# main.net
KiCad netlist of a schematic drawn in Altium Designer
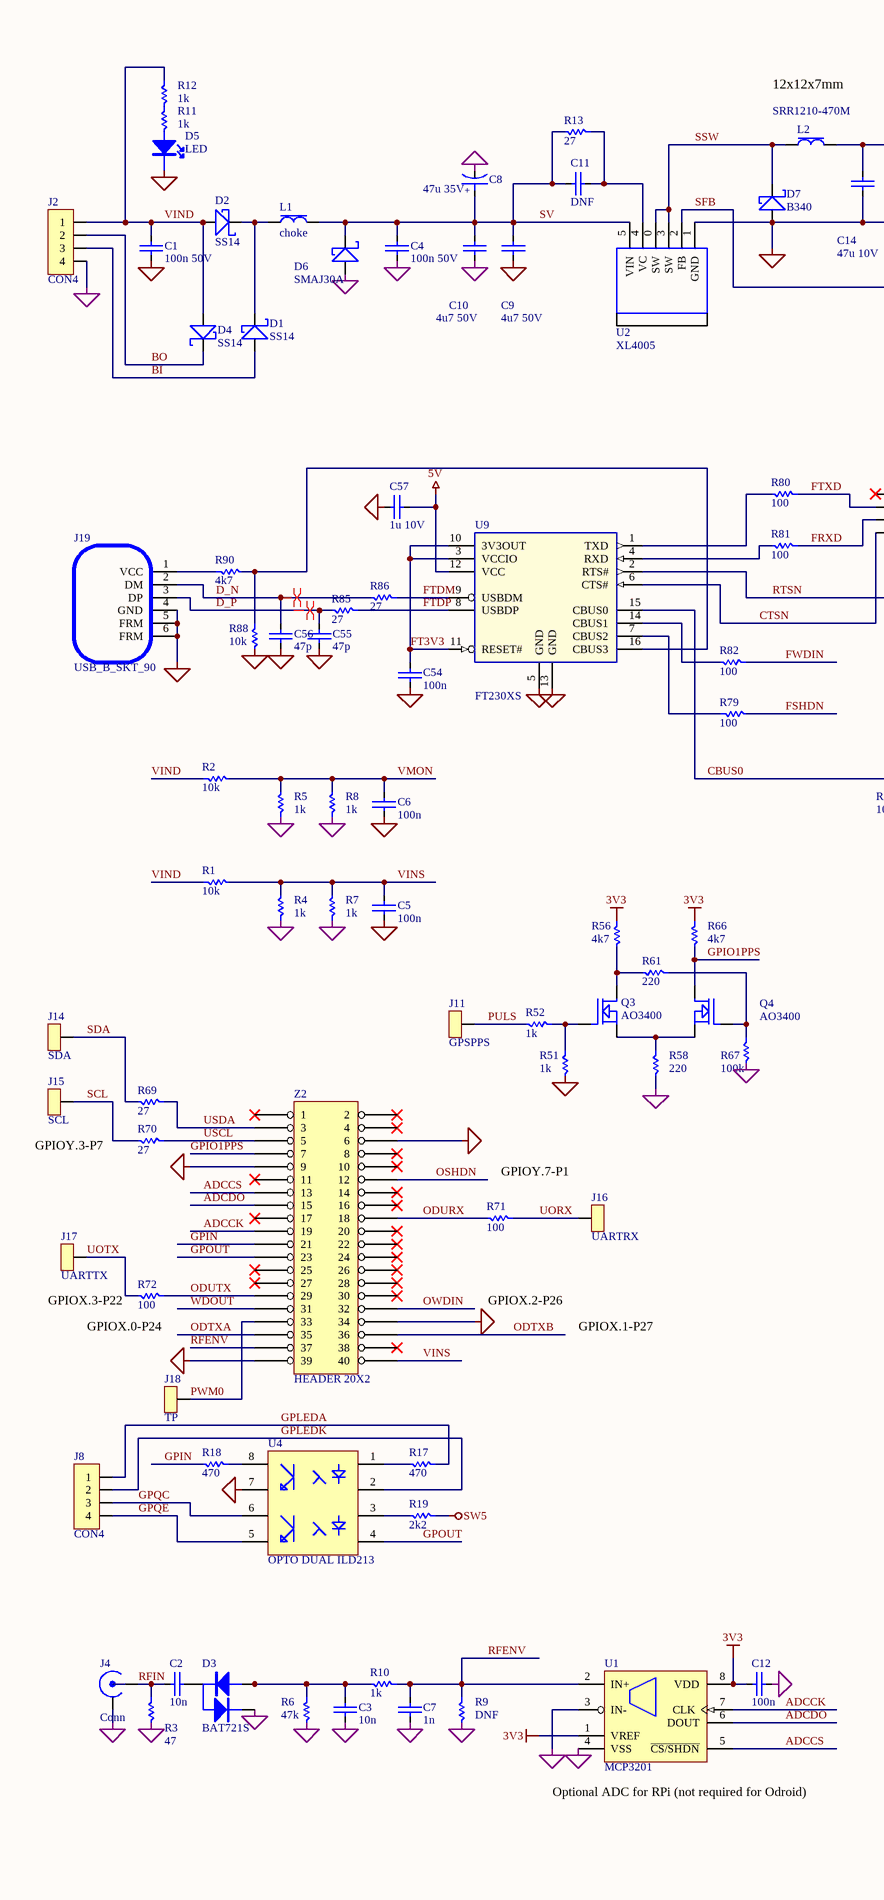
[diagram p0: main.SchDoc, left]
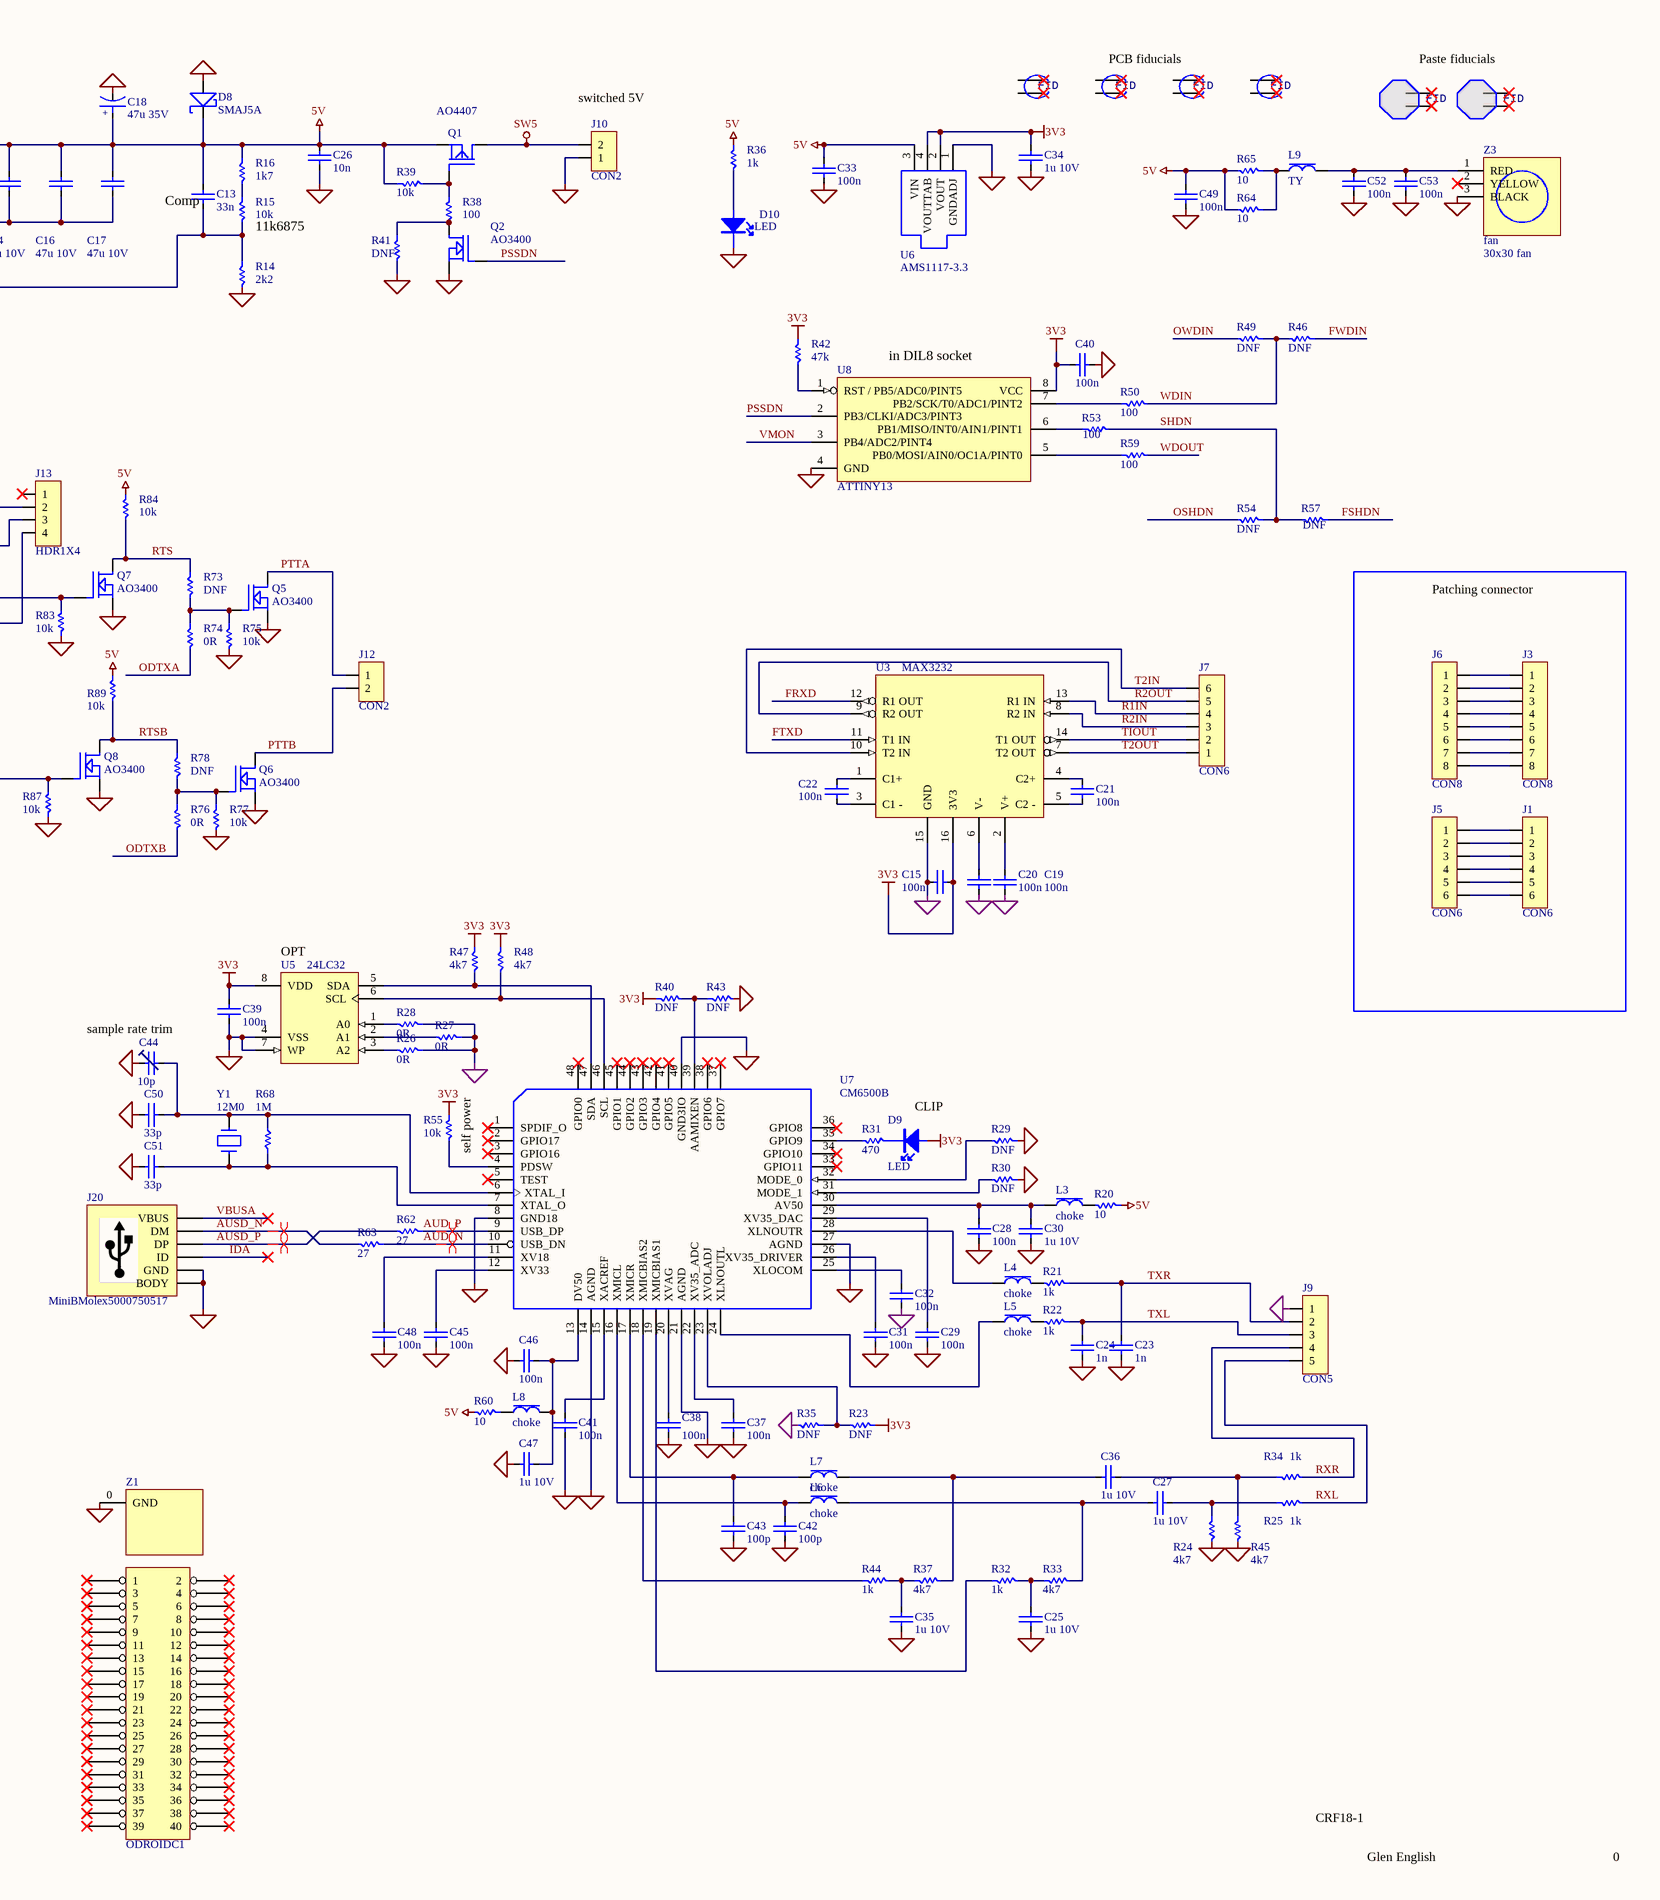
[diagram p1: main.SchDoc, right]

(export (version "E")
  (design (tool "Eeschema 10.0.6"))
  (components
    (comp (ref "C1")
      (value "100n 50V")
      (footprint "glensPCB:0603C")
      (libsource (lib "glen_sch") (part "CAPS"))
    )
    (comp (ref "C2") (value "10n") (footprint "glensPCB:0603C") (libsource (lib "glen_sch") (part "CAPS")))
    (comp (ref "C3") (value "10n") (footprint "glensPCB:0603C") (libsource (lib "glen_sch") (part "CAPS")))
    (comp (ref "C4")
      (value "100n 50V")
      (footprint "glensPCB:0603C")
      (libsource (lib "glen_sch") (part "CAPS"))
    )
    (comp (ref "C5") (value "100n") (footprint "glensPCB:0603C") (libsource (lib "glen_sch") (part "CAPS")))
    (comp (ref "C6") (value "100n") (footprint "glensPCB:0603C") (libsource (lib "glen_sch") (part "CAPS")))
    (comp (ref "C7") (value "1n") (footprint "glensPCB:0603C") (libsource (lib "glen_sch") (part "CAPS")))
    (comp (ref "C8")
      (value "47u 35V")
      (footprint "D_CASE_ELECTRO")
      (description "capacitor polarized")
      (libsource (lib "glen_sch") (part "CAP-POLS"))
    )
    (comp (ref "C9")
      (value "4u7 50V")
      (footprint "glensPCB:1206C")
      (libsource (lib "glen_sch") (part "CAPS"))
    )
    (comp (ref "C10")
      (value "4u7 50V")
      (footprint "glensPCB:1206C")
      (libsource (lib "glen_sch") (part "CAPS"))
    )
    (comp (ref "C11") (value "DNF") (footprint "glensPCB:0603C") (libsource (lib "glen_sch") (part "CAPS")))
    (comp (ref "C12") (value "100n") (footprint "glensPCB:0603C") (libsource (lib "glen_sch") (part "CAPS")))
    (comp (ref "C13") (value "33n") (footprint "glensPCB:0603C") (libsource (lib "glen_sch") (part "CAPS")))
    (comp (ref "C14")
      (value "47u 10V")
      (footprint "glensPCB:1206C")
      (libsource (lib "glen_sch") (part "CAPS"))
    )
    (comp (ref "C15") (value "100n") (footprint "glensPCB:0603C") (libsource (lib "glen_sch") (part "CAPS")))
    (comp (ref "C16")
      (value "47u 10V")
      (footprint "glensPCB:1206C")
      (libsource (lib "glen_sch") (part "CAPS"))
    )
    (comp (ref "C17")
      (value "47u 10V")
      (footprint "glensPCB:1206C")
      (libsource (lib "glen_sch") (part "CAPS"))
    )
    (comp (ref "C18")
      (value "47u 35V")
      (footprint "D_CASE_ELECTRO")
      (description "capacitor polarized")
      (libsource (lib "glen_sch") (part "CAP-POLS"))
    )
    (comp (ref "C19") (value "100n") (footprint "glensPCB:0603C") (libsource (lib "glen_sch") (part "CAPS")))
    (comp (ref "C20") (value "100n") (footprint "glensPCB:0603C") (libsource (lib "glen_sch") (part "CAPS")))
    (comp (ref "C21") (value "100n") (footprint "glensPCB:0603C") (libsource (lib "glen_sch") (part "CAPS")))
    (comp (ref "C22") (value "100n") (footprint "glensPCB:0603C") (libsource (lib "glen_sch") (part "CAPS")))
    (comp (ref "C23") (value "1n") (footprint "glensPCB:0603C") (libsource (lib "glen_sch") (part "CAPS")))
    (comp (ref "C24") (value "1n") (footprint "glensPCB:0603C") (libsource (lib "glen_sch") (part "CAPS")))
    (comp (ref "C25")
      (value "1u 10V")
      (footprint "glensPCB:0603C")
      (libsource (lib "glen_sch") (part "CAPS"))
    )
    (comp (ref "C26") (value "10n") (footprint "glensPCB:0603C") (libsource (lib "glen_sch") (part "CAPS")))
    (comp (ref "C27")
      (value "1u 10V")
      (footprint "glensPCB:0603C")
      (libsource (lib "glen_sch") (part "CAPS"))
    )
    (comp (ref "C28") (value "100n") (footprint "glensPCB:0603C") (libsource (lib "glen_sch") (part "CAPS")))
    (comp (ref "C29") (value "100n") (footprint "glensPCB:0603C") (libsource (lib "glen_sch") (part "CAPS")))
    (comp (ref "C30")
      (value "1u 10V")
      (footprint "glensPCB:0603C")
      (libsource (lib "glen_sch") (part "CAPS"))
    )
    (comp (ref "C31") (value "100n") (footprint "glensPCB:0603C") (libsource (lib "glen_sch") (part "CAPS")))
    (comp (ref "C32") (value "100n") (footprint "glensPCB:0603C") (libsource (lib "glen_sch") (part "CAPS")))
    (comp (ref "C33") (value "100n") (footprint "glensPCB:0603C") (libsource (lib "glen_sch") (part "CAPS")))
    (comp (ref "C34")
      (value "1u 10V")
      (footprint "glensPCB:0603C")
      (libsource (lib "glen_sch") (part "CAPS"))
    )
    (comp (ref "C35")
      (value "1u 10V")
      (footprint "glensPCB:0603C")
      (libsource (lib "glen_sch") (part "CAPS"))
    )
    (comp (ref "C36")
      (value "1u 10V")
      (footprint "glensPCB:0603C")
      (libsource (lib "glen_sch") (part "CAPS"))
    )
    (comp (ref "C37") (value "100n") (footprint "glensPCB:0603C") (libsource (lib "glen_sch") (part "CAPS")))
    (comp (ref "C38") (value "100n") (footprint "glensPCB:0603C") (libsource (lib "glen_sch") (part "CAPS")))
    (comp (ref "C39") (value "100n") (footprint "glensPCB:0603C") (libsource (lib "glen_sch") (part "CAPS")))
    (comp (ref "C40") (value "100n") (footprint "glensPCB:0603C") (libsource (lib "glen_sch") (part "CAPS")))
    (comp (ref "C41") (value "100n") (footprint "glensPCB:0603C") (libsource (lib "glen_sch") (part "CAPS")))
    (comp (ref "C42") (value "100p") (footprint "glensPCB:0603C") (libsource (lib "glen_sch") (part "CAPS")))
    (comp (ref "C43") (value "100p") (footprint "glensPCB:0603C") (libsource (lib "glen_sch") (part "CAPS")))
    (comp (ref "C44")
      (value "10p")
      (footprint "glensPCB:CAP0.1")
      (description "trimmer cap")
      (libsource (lib "glen_sch") (part "CAPTRIM"))
    )
    (comp (ref "C45") (value "100n") (footprint "glensPCB:0603C") (libsource (lib "glen_sch") (part "CAPS")))
    (comp (ref "C46") (value "100n") (footprint "glensPCB:0603C") (libsource (lib "glen_sch") (part "CAPS")))
    (comp (ref "C47")
      (value "1u 10V")
      (footprint "glensPCB:0603C")
      (libsource (lib "glen_sch") (part "CAPS"))
    )
    (comp (ref "C48") (value "100n") (footprint "glensPCB:0603C") (libsource (lib "glen_sch") (part "CAPS")))
    (comp (ref "C49") (value "100n") (footprint "glensPCB:0603C") (libsource (lib "glen_sch") (part "CAPS")))
    (comp (ref "C50") (value "33p") (footprint "glensPCB:0603C") (libsource (lib "glen_sch") (part "CAPS")))
    (comp (ref "C51") (value "33p") (footprint "glensPCB:0603C") (libsource (lib "glen_sch") (part "CAPS")))
    (comp (ref "C52") (value "100n") (footprint "glensPCB:0603C") (libsource (lib "glen_sch") (part "CAPS")))
    (comp (ref "C53") (value "100n") (footprint "glensPCB:0603C") (libsource (lib "glen_sch") (part "CAPS")))
    (comp (ref "C54") (value "100n") (footprint "glensPCB:0603C") (libsource (lib "glen_sch") (part "CAPS")))
    (comp (ref "C55") (value "47p") (footprint "glensPCB:0603C") (libsource (lib "glen_sch") (part "CAPS")))
    (comp (ref "C56") (value "47p") (footprint "glensPCB:0603C") (libsource (lib "glen_sch") (part "CAPS")))
    (comp (ref "C57")
      (value "1u 10V")
      (footprint "glensPCB:0603C")
      (libsource (lib "glen_sch") (part "CAPS"))
    )
    (comp (ref "D1")
      (value "SS14")
      (footprint "SMA_DIODE")
      (description "schottky")
      (libsource (lib "glen_sch") (part "DIODE_SHOTT_AK_SMALL"))
    )
    (comp (ref "D2")
      (value "SS14")
      (footprint "SMA_DIODE")
      (description "schottky")
      (libsource (lib "glen_sch") (part "DIODE_SHOTT_AK_SMALL"))
    )
    (comp (ref "D3")
      (value "BAT721S")
      (footprint "SOT23")
      (description "dual diode series")
      (libsource (lib "glen_sch") (part "BAT721A-DUALDIODE_COM_ANODE_1"))
    )
    (comp (ref "D4")
      (value "SS14")
      (footprint "SMA_DIODE")
      (description "schottky")
      (libsource (lib "glen_sch") (part "DIODE_SHOTT_AK_SMALL"))
    )
    (comp (ref "D5") (value "LED") (footprint "0805LED") (libsource (lib "glen_sch") (part "LEDS")))
    (comp (ref "D6")
      (value "SMAJ30A")
      (footprint "SMA_DIODE")
      (description "schottky")
      (libsource (lib "glen_sch") (part "DIODE_SHOTT_AK_SMALL"))
    )
    (comp (ref "D7")
      (value "B340")
      (footprint "SMB_diode")
      (description "schottky")
      (libsource (lib "glen_sch") (part "DIODE_SHOTT_AK_SMALL"))
    )
    (comp (ref "D8")
      (value "SMAJ5A")
      (footprint "SMA_DIODE")
      (description "schottky")
      (libsource (lib "glen_sch") (part "DIODE_SHOTT_AK_SMALL"))
    )
    (comp (ref "D9") (value "LED") (footprint "0805LED") (libsource (lib "glen_sch") (part "LEDS")))
    (comp (ref "D10") (value "LED") (footprint "0805LED") (libsource (lib "glen_sch") (part "LEDS")))
    (comp (ref "FID1")
      (value "FIDUCIAL")
      (footprint "FIDUCIAL")
      (description "fiducial mark")
      (libsource (lib "glen_sch") (part "FIDUCIAL"))
    )
    (comp (ref "FID2")
      (value "FIDUCIAL")
      (footprint "FIDUCIAL")
      (description "fiducial mark")
      (libsource (lib "glen_sch") (part "FIDUCIAL"))
    )
    (comp (ref "FID3")
      (value "FIDUCIAL")
      (footprint "FIDUCIAL")
      (description "fiducial mark")
      (libsource (lib "glen_sch") (part "FIDUCIAL"))
    )
    (comp (ref "FID4")
      (value "FIDUCIAL")
      (footprint "FIDUCIAL")
      (description "fiducial mark")
      (libsource (lib "glen_sch") (part "FIDUCIAL"))
    )
    (comp (ref "J1") (value "CON6") (footprint "SL3.81/6/90G") (libsource (lib "Device") (part "CON6")))
    (comp (ref "J2") (value "CON4") (footprint "SL3.81/4/90G") (libsource (lib "Device") (part "CON4")))
    (comp (ref "J3") (value "CON8") (footprint "SL3.81/8/90G") (libsource (lib "Device") (part "CON8")))
    (comp (ref "J4")
      (value "Conn")
      (footprint "SMA_COMPACT_VERTICAL_PCB")
      (description "coax connector")
      (libsource (lib "glen_sch") (part "CoaxConn"))
    )
    (comp (ref "J5") (value "CON6") (footprint "HDR1X6") (libsource (lib "") (part "CON6_1")))
    (comp (ref "J6") (value "CON8") (footprint "HDR1X8") (libsource (lib "") (part "CON8_1")))
    (comp (ref "J7") (value "CON6") (footprint "HDR1X6") (libsource (lib "") (part "CON6_2")))
    (comp (ref "J8") (value "CON4") (footprint "HDR1X4") (libsource (lib "Device") (part "CON4")))
    (comp (ref "J9") (value "CON5") (footprint "HDR1X5") (libsource (lib "Device") (part "CON5")))
    (comp (ref "J10") (value "CON2") (footprint "HDR1X2") (libsource (lib "") (part "CON2_1")))
    (comp (ref "J11")
      (value "GPSPPS")
      (footprint "GPPAD")
      (description "test point")
      (libsource (lib "glen_sch") (part "TESTPOINT"))
    )
    (comp (ref "J12") (value "CON2") (footprint "HDR1X2") (libsource (lib "Device") (part "CON2")))
    (comp (ref "J13") (value "HDR1X4") (footprint "HDR1X4") (libsource (lib "") (part "CON4_1")))
    (comp (ref "J14")
      (value "SDA")
      (footprint "GPPAD")
      (description "test point")
      (libsource (lib "glen_sch") (part "TESTPOINT"))
    )
    (comp (ref "J15")
      (value "SCL")
      (footprint "GPPAD")
      (description "test point")
      (libsource (lib "glen_sch") (part "TESTPOINT"))
    )
    (comp (ref "J16")
      (value "UARTRX")
      (footprint "GPPAD")
      (description "test point")
      (libsource (lib "") (part "TESTPOINT_1"))
    )
    (comp (ref "J17")
      (value "UARTTX")
      (footprint "GPPAD")
      (description "test point")
      (libsource (lib "glen_sch") (part "TESTPOINT"))
    )
    (comp (ref "J18")
      (value "TP")
      (footprint "GPPAD")
      (description "test point")
      (libsource (lib "glen_sch") (part "TESTPOINT"))
    )
    (comp (ref "J19")
      (value "USB_B_SKT_90")
      (footprint "USB_B_SKT_90")
      (libsource (lib "Device") (part "USB_B_SKT"))
    )
    (comp (ref "J20")
      (value "MiniBMolex5000750517")
      (footprint "USB_UX60A-MB-5ST")
      (description "USB socket miniB")
      (libsource (lib "glen_sch") (part "USB_MiniB_molex"))
    )
    (comp (ref "L1") (value "choke") (footprint "1812L") (libsource (lib "glen_sch") (part "INDUCTORSHORT")))
    (comp (ref "L2")
      (value "SRR1210-470M")
      (footprint "BOURNS_SRR1210")
      (description "XAL4040-103")
      (libsource (lib "glen_sch") (part "INDUCTORSHORT"))
    )
    (comp (ref "L3") (value "choke") (footprint "0603L") (libsource (lib "glen_sch") (part "INDUCTORSHORT")))
    (comp (ref "L4") (value "choke") (footprint "0603L") (libsource (lib "glen_sch") (part "INDUCTORSHORT")))
    (comp (ref "L5") (value "choke") (footprint "0603L") (libsource (lib "glen_sch") (part "INDUCTORSHORT")))
    (comp (ref "L6") (value "choke") (footprint "0603L") (libsource (lib "glen_sch") (part "INDUCTORSHORT")))
    (comp (ref "L7") (value "choke") (footprint "0603L") (libsource (lib "glen_sch") (part "INDUCTORSHORT")))
    (comp (ref "L8") (value "choke") (footprint "0603L") (libsource (lib "glen_sch") (part "INDUCTORSHORT")))
    (comp (ref "L9") (value "TY") (footprint "0805L") (libsource (lib "glen_sch") (part "INDUCTORSHORT")))
    (comp (ref "PFID1")
      (value "PASTEFID")
      (footprint "FIDUCIAL_PASTE")
      (description "fiducial mark paste")
      (libsource (lib "glen_sch") (part "FIDUCIAL_PASTE"))
    )
    (comp (ref "PFID2")
      (value "PASTEFID")
      (footprint "FIDUCIAL_PASTE")
      (description "fiducial mark paste")
      (libsource (lib "glen_sch") (part "FIDUCIAL_PASTE"))
    )
    (comp (ref "Q1")
      (value "AO4407")
      (footprint "SO8FET")
      (description "mosfet digital")
      (libsource (lib "glen_sch") (part "FDC638P"))
    )
    (comp (ref "Q2")
      (value "AO3400")
      (footprint "FDV-301N_SOT23")
      (description "FDV301N")
      (libsource (lib "glen_sch") (part "MOSFET-DIGITAL-SOT-23_1"))
    )
    (comp (ref "Q3")
      (value "AO3400")
      (footprint "FDV-301N_SOT23")
      (description "FDV301N")
      (libsource (lib "glen_sch") (part "MOSFET-DIGITAL-SOT-23_1"))
    )
    (comp (ref "Q4")
      (value "AO3400")
      (footprint "FDV-301N_SOT23")
      (description "FDV301N")
      (libsource (lib "glen_sch") (part "MOSFET-DIGITAL-SOT-23_1"))
    )
    (comp (ref "Q5")
      (value "AO3400")
      (footprint "FDV-301N_SOT23")
      (description "FDV301N")
      (libsource (lib "glen_sch") (part "MOSFET-DIGITAL-SOT-23_1"))
    )
    (comp (ref "Q6")
      (value "AO3400")
      (footprint "FDV-301N_SOT23")
      (description "FDV301N")
      (libsource (lib "glen_sch") (part "MOSFET-DIGITAL-SOT-23_1"))
    )
    (comp (ref "Q7")
      (value "AO3400")
      (footprint "FDV-301N_SOT23")
      (description "FDV301N")
      (libsource (lib "glen_sch") (part "MOSFET-DIGITAL-SOT-23_1"))
    )
    (comp (ref "Q8")
      (value "AO3400")
      (footprint "FDV-301N_SOT23")
      (description "FDV301N")
      (libsource (lib "glen_sch") (part "MOSFET-DIGITAL-SOT-23_1"))
    )
    (comp (ref "R1")
      (value "10k")
      (footprint "0603R")
      (description "resistor small")
      (libsource (lib "glen_sch") (part "RESS"))
    )
    (comp (ref "R2")
      (value "10k")
      (footprint "0603R")
      (description "resistor small")
      (libsource (lib "glen_sch") (part "RESS"))
    )
    (comp (ref "R3")
      (value "47")
      (footprint "0603R")
      (description "resistor small")
      (libsource (lib "glen_sch") (part "RESS"))
    )
    (comp (ref "R4")
      (value "1k")
      (footprint "0603R")
      (description "resistor small")
      (libsource (lib "glen_sch") (part "RESS"))
    )
    (comp (ref "R5")
      (value "1k")
      (footprint "0603R")
      (description "resistor small")
      (libsource (lib "glen_sch") (part "RESS"))
    )
    (comp (ref "R6")
      (value "47k")
      (footprint "0603R")
      (description "resistor small")
      (libsource (lib "glen_sch") (part "RESS"))
    )
    (comp (ref "R7")
      (value "1k")
      (footprint "0603R")
      (description "resistor small")
      (libsource (lib "glen_sch") (part "RESS"))
    )
    (comp (ref "R8")
      (value "1k")
      (footprint "0603R")
      (description "resistor small")
      (libsource (lib "glen_sch") (part "RESS"))
    )
    (comp (ref "R9")
      (value "DNF")
      (footprint "0603R")
      (description "resistor small")
      (libsource (lib "glen_sch") (part "RESS"))
    )
    (comp (ref "R10")
      (value "1k")
      (footprint "0603R")
      (description "resistor small")
      (libsource (lib "glen_sch") (part "RESS"))
    )
    (comp (ref "R11")
      (value "1k")
      (footprint "0603R")
      (description "resistor small")
      (libsource (lib "glen_sch") (part "RESS"))
    )
    (comp (ref "R12")
      (value "1k")
      (footprint "0603R")
      (description "resistor small")
      (libsource (lib "glen_sch") (part "RESS"))
    )
    (comp (ref "R13")
      (value "27")
      (footprint "0603R")
      (description "resistor small")
      (libsource (lib "glen_sch") (part "RESS"))
    )
    (comp (ref "R14")
      (value "2k2")
      (footprint "0603R")
      (description "resistor small")
      (libsource (lib "glen_sch") (part "RESS"))
    )
    (comp (ref "R15")
      (value "10k")
      (footprint "0603R")
      (description "resistor small")
      (libsource (lib "glen_sch") (part "RESS"))
    )
    (comp (ref "R16")
      (value "1k7")
      (footprint "0603R")
      (description "resistor small")
      (libsource (lib "glen_sch") (part "RESS"))
    )
    (comp (ref "R17")
      (value "470")
      (footprint "0603R")
      (description "resistor small")
      (libsource (lib "glen_sch") (part "RESS"))
    )
    (comp (ref "R18")
      (value "470")
      (footprint "0603R")
      (description "resistor small")
      (libsource (lib "glen_sch") (part "RESS"))
    )
    (comp (ref "R19")
      (value "2k2")
      (footprint "0603R")
      (description "resistor small")
      (libsource (lib "glen_sch") (part "RESS"))
    )
    (comp (ref "R20")
      (value "10")
      (footprint "0603R")
      (description "resistor small")
      (libsource (lib "glen_sch") (part "RESS"))
    )
    (comp (ref "R21")
      (value "1k")
      (footprint "0603R")
      (description "resistor small")
      (libsource (lib "glen_sch") (part "RESS"))
    )
    (comp (ref "R22")
      (value "1k")
      (footprint "0603R")
      (description "resistor small")
      (libsource (lib "glen_sch") (part "RESS"))
    )
    (comp (ref "R23")
      (value "DNF")
      (footprint "0603R")
      (description "resistor small")
      (libsource (lib "glen_sch") (part "RESS"))
    )
    (comp (ref "R24")
      (value "4k7")
      (footprint "0603R")
      (description "resistor small")
      (libsource (lib "glen_sch") (part "RESS"))
    )
    (comp (ref "R25")
      (value "1k")
      (footprint "0603R")
      (description "resistor small")
      (libsource (lib "glen_sch") (part "RESS"))
    )
    (comp (ref "R26")
      (value "0R")
      (footprint "0603R")
      (description "resistor small")
      (libsource (lib "glen_sch") (part "RESS"))
    )
    (comp (ref "R27")
      (value "0R")
      (footprint "0603R")
      (description "resistor small")
      (libsource (lib "glen_sch") (part "RESS"))
    )
    (comp (ref "R28")
      (value "0R")
      (footprint "0603R")
      (description "resistor small")
      (libsource (lib "glen_sch") (part "RESS"))
    )
    (comp (ref "R29")
      (value "DNF")
      (footprint "0603R")
      (description "resistor small")
      (libsource (lib "glen_sch") (part "RESS"))
    )
    (comp (ref "R30")
      (value "DNF")
      (footprint "0603R")
      (description "resistor small")
      (libsource (lib "glen_sch") (part "RESS"))
    )
    (comp (ref "R31")
      (value "470")
      (footprint "0603R")
      (description "resistor small")
      (libsource (lib "glen_sch") (part "RESS"))
    )
    (comp (ref "R32")
      (value "1k")
      (footprint "0603R")
      (description "resistor small")
      (libsource (lib "glen_sch") (part "RESS"))
    )
    (comp (ref "R33")
      (value "4k7")
      (footprint "0603R")
      (description "resistor small")
      (libsource (lib "glen_sch") (part "RESS"))
    )
    (comp (ref "R34")
      (value "1k")
      (footprint "0603R")
      (description "resistor small")
      (libsource (lib "glen_sch") (part "RESS"))
    )
    (comp (ref "R35")
      (value "DNF")
      (footprint "0603R")
      (description "resistor small")
      (libsource (lib "glen_sch") (part "RESS"))
    )
    (comp (ref "R36")
      (value "1k")
      (footprint "0603R")
      (description "resistor small")
      (libsource (lib "glen_sch") (part "RESS"))
    )
    (comp (ref "R37")
      (value "4k7")
      (footprint "0603R")
      (description "resistor small")
      (libsource (lib "glen_sch") (part "RESS"))
    )
    (comp (ref "R38")
      (value "100")
      (footprint "0603R")
      (description "resistor small")
      (libsource (lib "glen_sch") (part "RESS"))
    )
    (comp (ref "R39")
      (value "10k")
      (footprint "0603R")
      (description "resistor small")
      (libsource (lib "glen_sch") (part "RESS"))
    )
    (comp (ref "R40")
      (value "DNF")
      (footprint "0603R")
      (description "resistor small")
      (libsource (lib "glen_sch") (part "RESS"))
    )
    (comp (ref "R41")
      (value "DNF")
      (footprint "0603R")
      (description "resistor small")
      (libsource (lib "glen_sch") (part "RESS"))
    )
    (comp (ref "R42")
      (value "47k")
      (footprint "0603R")
      (description "resistor small")
      (libsource (lib "glen_sch") (part "RESS"))
    )
    (comp (ref "R43")
      (value "DNF")
      (footprint "0603R")
      (description "resistor small")
      (libsource (lib "glen_sch") (part "RESS"))
    )
    (comp (ref "R44")
      (value "1k")
      (footprint "0603R")
      (description "resistor small")
      (libsource (lib "glen_sch") (part "RESS"))
    )
    (comp (ref "R45")
      (value "4k7")
      (footprint "0603R")
      (description "resistor small")
      (libsource (lib "glen_sch") (part "RESS"))
    )
    (comp (ref "R46")
      (value "DNF")
      (footprint "0603R")
      (description "resistor small")
      (libsource (lib "glen_sch") (part "RESS"))
    )
    (comp (ref "R47")
      (value "4k7")
      (footprint "0603R")
      (description "resistor small")
      (libsource (lib "glen_sch") (part "RESS"))
    )
    (comp (ref "R48")
      (value "4k7")
      (footprint "0603R")
      (description "resistor small")
      (libsource (lib "glen_sch") (part "RESS"))
    )
    (comp (ref "R49")
      (value "DNF")
      (footprint "0603R")
      (description "resistor small")
      (libsource (lib "glen_sch") (part "RESS"))
    )
    (comp (ref "R50")
      (value "100")
      (footprint "0603R")
      (description "resistor small")
      (libsource (lib "glen_sch") (part "RESS"))
    )
    (comp (ref "R51")
      (value "1k")
      (footprint "0603R")
      (description "resistor small")
      (libsource (lib "glen_sch") (part "RESS"))
    )
    (comp (ref "R52")
      (value "1k")
      (footprint "0603R")
      (description "resistor small")
      (libsource (lib "glen_sch") (part "RESS"))
    )
    (comp (ref "R53")
      (value "100")
      (footprint "0603R")
      (description "resistor small")
      (libsource (lib "glen_sch") (part "RESS"))
    )
    (comp (ref "R54")
      (value "DNF")
      (footprint "0603R")
      (description "resistor small")
      (libsource (lib "glen_sch") (part "RESS"))
    )
    (comp (ref "R55")
      (value "10k")
      (footprint "0603R")
      (description "resistor small")
      (libsource (lib "glen_sch") (part "RESS"))
    )
    (comp (ref "R56")
      (value "4k7")
      (footprint "0603R")
      (description "resistor small")
      (libsource (lib "glen_sch") (part "RESS"))
    )
    (comp (ref "R57")
      (value "DNF")
      (footprint "0603R")
      (description "resistor small")
      (libsource (lib "glen_sch") (part "RESS"))
    )
    (comp (ref "R58")
      (value "220")
      (footprint "0603R")
      (description "resistor small")
      (libsource (lib "glen_sch") (part "RESS"))
    )
    (comp (ref "R59")
      (value "100")
      (footprint "0603R")
      (description "resistor small")
      (libsource (lib "glen_sch") (part "RESS"))
    )
    (comp (ref "R60")
      (value "10")
      (footprint "0603R")
      (description "resistor small")
      (libsource (lib "glen_sch") (part "RESS"))
    )
    (comp (ref "R61")
      (value "220")
      (footprint "0603R")
      (description "resistor small")
      (libsource (lib "glen_sch") (part "RESS"))
    )
    (comp (ref "R62")
      (value "27")
      (footprint "0603R")
      (description "resistor small")
      (libsource (lib "glen_sch") (part "RESS"))
    )
    (comp (ref "R63")
      (value "27")
      (footprint "0603R")
      (description "resistor small")
      (libsource (lib "glen_sch") (part "RESS"))
    )
    (comp (ref "R64")
      (value "10")
      (footprint "1206R")
      (description "resistor small")
      (libsource (lib "glen_sch") (part "RESS"))
    )
    (comp (ref "R65")
      (value "10")
      (footprint "1206R")
      (description "resistor small")
      (libsource (lib "glen_sch") (part "RESS"))
    )
    (comp (ref "R66")
      (value "4k7")
      (footprint "0603R")
      (description "resistor small")
      (libsource (lib "glen_sch") (part "RESS"))
    )
    (comp (ref "R67")
      (value "100k")
      (footprint "0603R")
      (description "resistor small")
      (libsource (lib "glen_sch") (part "RESS"))
    )
    (comp (ref "R68")
      (value "1M")
      (footprint "0603R")
      (description "resistor small")
      (libsource (lib "glen_sch") (part "RESS"))
    )
    (comp (ref "R69")
      (value "27")
      (footprint "0603R")
      (description "resistor small")
      (libsource (lib "glen_sch") (part "RESS"))
    )
    (comp (ref "R70")
      (value "27")
      (footprint "0603R")
      (description "resistor small")
      (libsource (lib "glen_sch") (part "RESS"))
    )
    (comp (ref "R71")
      (value "100")
      (footprint "0603R")
      (description "resistor small")
      (libsource (lib "glen_sch") (part "RESS"))
    )
    (comp (ref "R72")
      (value "100")
      (footprint "0603R")
      (description "resistor small")
      (libsource (lib "glen_sch") (part "RESS"))
    )
    (comp (ref "R73")
      (value "DNF")
      (footprint "0603R")
      (description "resistor small")
      (libsource (lib "glen_sch") (part "RESS"))
    )
    (comp (ref "R74")
      (value "0R")
      (footprint "0603R")
      (description "resistor small")
      (libsource (lib "glen_sch") (part "RESS"))
    )
    (comp (ref "R75")
      (value "10k")
      (footprint "0603R")
      (description "resistor small")
      (libsource (lib "glen_sch") (part "RESS"))
    )
    (comp (ref "R76")
      (value "0R")
      (footprint "0603R")
      (description "resistor small")
      (libsource (lib "glen_sch") (part "RESS"))
    )
    (comp (ref "R77")
      (value "10k")
      (footprint "0603R")
      (description "resistor small")
      (libsource (lib "glen_sch") (part "RESS"))
    )
    (comp (ref "R78")
      (value "DNF")
      (footprint "0603R")
      (description "resistor small")
      (libsource (lib "glen_sch") (part "RESS"))
    )
    (comp (ref "R79")
      (value "100")
      (footprint "0603R")
      (description "resistor small")
      (libsource (lib "glen_sch") (part "RESS"))
    )
    (comp (ref "R80")
      (value "100")
      (footprint "0603R")
      (description "resistor small")
      (libsource (lib "glen_sch") (part "RESS"))
    )
    (comp (ref "R81")
      (value "100")
      (footprint "0603R")
      (description "resistor small")
      (libsource (lib "glen_sch") (part "RESS"))
    )
    (comp (ref "R82")
      (value "100")
      (footprint "0603R")
      (description "resistor small")
      (libsource (lib "glen_sch") (part "RESS"))
    )
    (comp (ref "R83")
      (value "10k")
      (footprint "0603R")
      (description "resistor small")
      (libsource (lib "glen_sch") (part "RESS"))
    )
    (comp (ref "R84")
      (value "10k")
      (footprint "0603R")
      (description "resistor small")
      (libsource (lib "glen_sch") (part "RESS"))
    )
    (comp (ref "R85")
      (value "27")
      (footprint "0603R")
      (description "resistor small")
      (libsource (lib "glen_sch") (part "RESS"))
    )
    (comp (ref "R86")
      (value "27")
      (footprint "0603R")
      (description "resistor small")
      (libsource (lib "glen_sch") (part "RESS"))
    )
    (comp (ref "R87")
      (value "10k")
      (footprint "0603R")
      (description "resistor small")
      (libsource (lib "glen_sch") (part "RESS"))
    )
    (comp (ref "R88")
      (value "10k")
      (footprint "0603R")
      (description "resistor small")
      (libsource (lib "glen_sch") (part "RESS"))
    )
    (comp (ref "R89")
      (value "10k")
      (footprint "0603R")
      (description "resistor small")
      (libsource (lib "glen_sch") (part "RESS"))
    )
    (comp (ref "R90")
      (value "4k7")
      (footprint "0603R")
      (description "resistor small")
      (libsource (lib "glen_sch") (part "RESS"))
    )
    (comp (ref "U1")
      (value "MCP3201")
      (footprint "DIP8")
      (description "12bit 2 channel 55kbps spi adc")
      (libsource (lib "glen_sch") (part "MCP3201"))
    )
    (comp (ref "U2")
      (value "XL4005")
      (footprint "TO263-5")
      (description "buck regulator 4A")
      (libsource (lib "glen_sch") (part "XL4015"))
    )
    (comp (ref "U3")
      (value "MAX3232")
      (footprint "SO16")
      (description "3.3V rs232 transceiver")
      (libsource (lib "glen_sch") (part "MAX3232"))
    )
    (comp (ref "U4")
      (value "OPTO DUAL ILD213")
      (footprint "SO8")
      (description "dual sm opto Vishay")
      (libsource (lib "glen_sch") (part "OPTO DUAL ILD213"))
    )
    (comp (ref "U5")
      (value "24LC32")
      (footprint "SO8")
      (description "eeprom 8 pin")
      (libsource (lib "glen_sch") (part "24C_EEPROM"))
    )
    (comp (ref "U6")
      (value "AMS1117-3.3")
      (footprint "SOT223")
      (description "3.3V LDO")
      (libsource (lib "glen_sch") (part "AMS1117"))
    )
    (comp (ref "U7")
      (value "CM6500B")
      (footprint "QFP48_7x7")
      (description "USB audio")
      (libsource (lib "glen_sch") (part "CM6500B"))
    )
    (comp (ref "U8")
      (value "ATTINY13")
      (footprint "DIP8")
      (description "microcontroller")
      (libsource (lib "glen_sch") (part "ATTINY13"))
    )
    (comp (ref "U9")
      (value "FT230XS")
      (footprint "TSSOP16")
      (description "ftdi uart ssop16")
      (libsource (lib "glen_sch") (part "FT230XS"))
    )
    (comp (ref "Y1") (value "12M0") (footprint "HC49") (libsource (lib "glen_sch") (part "CRYSTAL")))
    (comp (ref "Z1")
      (value "ODROIDC1")
      (footprint "ODROID_C1")
      (description "ODROID SBC")
      (libsource (lib "glen_sch") (part "ODROIDC1"))
    )
    (comp (ref "Z2")
      (value "HEADER 20X2")
      (footprint "HDR2X20_100MIL")
      (libsource (lib "Device") (part "HEADER 20X2"))
    )
    (comp (ref "Z3")
      (value "fan")
      (footprint "FAN_SUNON_MC3006")
      (description "sunon fan")
      (libsource (lib "Device") (part "Fan_Sunon_maglev_MC3006"))
    )
  )
  (nets
    (net (code "1") (name "/ADCCK") (class "Default")
      (node (ref "U1") (pin "7") (pinfunction "CLK_7") (pintype "input"))
      (node (ref "Z2") (pin "19") (pinfunction "19_19") (pintype "passive"))
    )
    (net (code "2") (name "/ADCCS") (class "Default")
      (node (ref "U1") (pin "5") (pinfunction "CS/SHDN_5") (pintype "passive"))
      (node (ref "Z2") (pin "13") (pinfunction "13_13") (pintype "passive"))
    )
    (net (code "3") (name "/ADCDO") (class "Default")
      (node (ref "U1") (pin "6") (pinfunction "DOUT_6") (pintype "passive"))
      (node (ref "Z2") (pin "15") (pinfunction "15_15") (pintype "passive"))
    )
    (net (code "4") (name "/AUD_N") (class "Default")
      (node (ref "R63") (pin "1") (pinfunction "1_1") (pintype "passive"))
      (node (ref "U7") (pin "10") (pinfunction "USB_DN_10") (pintype "passive"))
    )
    (net (code "5") (name "/AUD_P") (class "Default")
      (node (ref "R62") (pin "1") (pinfunction "1_1") (pintype "passive"))
      (node (ref "U7") (pin "9") (pinfunction "USB_DP_9") (pintype "passive"))
    )
    (net (code "6") (name "/AUSD_N") (class "Default")
      (node (ref "J20") (pin "DM") (pinfunction "DM_DM") (pintype "passive"))
      (node (ref "R63") (pin "2") (pinfunction "2_2") (pintype "passive"))
    )
    (net (code "7") (name "/AUSD_P") (class "Default")
      (node (ref "J20") (pin "DP") (pinfunction "DP_DP") (pintype "passive"))
      (node (ref "R62") (pin "2") (pinfunction "2_2") (pintype "passive"))
    )
    (net (code "8") (name "/BI") (class "Default")
      (node (ref "D1") (pin "A") (pinfunction "ANODE_A") (pintype "passive"))
      (node (ref "J2") (pin "3") (pinfunction "3_3") (pintype "passive"))
    )
    (net (code "9") (name "/BO") (class "Default")
      (node (ref "D4") (pin "K") (pinfunction "CATHODE_K") (pintype "passive"))
      (node (ref "J2") (pin "2") (pinfunction "2_2") (pintype "passive"))
    )
    (net (code "10") (name "/CBUS0") (class "Default")
      (node (ref "Q8") (pin "G") (pintype "passive"))
      (node (ref "R87") (pin "2") (pinfunction "2_2") (pintype "passive"))
      (node (ref "U9") (pin "15") (pinfunction "CBUS0_15") (pintype "passive"))
    )
    (net (code "11") (name "/CTSN") (class "Default")
      (node (ref "J13") (pin "4") (pinfunction "4_4") (pintype "passive"))
      (node (ref "U9") (pin "6") (pinfunction "CTS#_6") (pintype "input"))
    )
    (net (code "12") (name "/D_N") (class "Default")
      (node (ref "C56") (pin "2") (pintype "passive"))
      (node (ref "J19") (pin "2") (pinfunction "DM_2") (pintype "passive"))
      (node (ref "R86") (pin "2") (pinfunction "2_2") (pintype "passive"))
    )
    (net (code "13") (name "/D_P") (class "Default")
      (node (ref "C55") (pin "2") (pintype "passive"))
      (node (ref "J19") (pin "3") (pinfunction "DP_3") (pintype "passive"))
      (node (ref "R85") (pin "2") (pinfunction "2_2") (pintype "passive"))
    )
    (net (code "14") (name "/FRXD") (class "Default")
      (node (ref "J13") (pin "3") (pinfunction "3_3") (pintype "passive"))
      (node (ref "R81") (pin "1") (pinfunction "1_1") (pintype "passive"))
      (node (ref "U3") (pin "12") (pinfunction "R1_OUT_12") (pintype "output"))
    )
    (net (code "15") (name "/FSHDN") (class "Default")
      (node (ref "R57") (pin "1") (pinfunction "1_1") (pintype "passive"))
      (node (ref "R79") (pin "2") (pinfunction "2_2") (pintype "passive"))
    )
    (net (code "16") (name "/FT3V3") (class "Default")
      (node (ref "C54") (pin "1") (pintype "passive"))
      (node (ref "U9") (pin "10") (pinfunction "3V3OUT_10") (pintype "passive"))
      (node (ref "U9") (pin "11") (pinfunction "RESET#_11") (pintype "input"))
      (node (ref "U9") (pin "3") (pinfunction "VCCIO_3") (pintype "passive"))
    )
    (net (code "17") (name "/FTDM") (class "Default")
      (node (ref "R86") (pin "1") (pinfunction "1_1") (pintype "passive"))
      (node (ref "U9") (pin "9") (pinfunction "USBDM_9") (pintype "passive"))
    )
    (net (code "18") (name "/FTDP") (class "Default")
      (node (ref "R85") (pin "1") (pinfunction "1_1") (pintype "passive"))
      (node (ref "U9") (pin "8") (pinfunction "USBDP_8") (pintype "passive"))
    )
    (net (code "19") (name "/FTXD") (class "Default")
      (node (ref "J13") (pin "2") (pinfunction "2_2") (pintype "passive"))
      (node (ref "R80") (pin "1") (pinfunction "1_1") (pintype "passive"))
      (node (ref "U3") (pin "11") (pinfunction "T1_IN_11") (pintype "input"))
    )
    (net (code "20") (name "/FWDIN") (class "Default")
      (node (ref "R46") (pin "1") (pinfunction "1_1") (pintype "passive"))
      (node (ref "R82") (pin "1") (pinfunction "1_1") (pintype "passive"))
    )
    (net (code "21") (name "/GPIN") (class "Default")
      (node (ref "R18") (pin "2") (pinfunction "2_2") (pintype "passive"))
      (node (ref "Z2") (pin "21") (pinfunction "21_21") (pintype "passive"))
    )
    (net (code "22") (name "/GPIO1PPS") (class "Default")
      (node (ref "Q4") (pin "D") (pintype "passive"))
      (node (ref "R66") (pin "2") (pinfunction "2_2") (pintype "passive"))
      (node (ref "Z2") (pin "7") (pinfunction "7_7") (pintype "passive"))
    )
    (net (code "23") (name "/GPLEDA") (class "Default")
      (node (ref "J8") (pin "1") (pinfunction "1_1") (pintype "passive"))
      (node (ref "R17") (pin "1") (pinfunction "1_1") (pintype "passive"))
    )
    (net (code "24") (name "/GPLEDK") (class "Default")
      (node (ref "J8") (pin "2") (pinfunction "2_2") (pintype "passive"))
      (node (ref "U4") (pin "2") (pinfunction "1K_2") (pintype "passive"))
    )
    (net (code "25") (name "/GPOUT") (class "Default")
      (node (ref "U4") (pin "4") (pinfunction "2K_4") (pintype "passive"))
      (node (ref "Z2") (pin "23") (pinfunction "23_23") (pintype "passive"))
    )
    (net (code "26") (name "/GPQC") (class "Default")
      (node (ref "J8") (pin "3") (pinfunction "3_3") (pintype "passive"))
      (node (ref "U4") (pin "6") (pinfunction "2C_6") (pintype "passive"))
    )
    (net (code "27") (name "/GPQE") (class "Default")
      (node (ref "J8") (pin "4") (pinfunction "4_4") (pintype "passive"))
      (node (ref "U4") (pin "5") (pinfunction "2E_5") (pintype "passive"))
    )
    (net (code "28") (name "/IDA") (class "Default")
      (node (ref "J20") (pin "ID") (pinfunction "ID_ID") (pintype "passive+no_connect"))
    )
    (net (code "29") (name "/ODTXA") (class "Default")
      (node (ref "R74") (pin "2") (pinfunction "2_2") (pintype "passive"))
      (node (ref "Z2") (pin "35") (pinfunction "35_35") (pintype "passive"))
    )
    (net (code "30") (name "/ODTXB") (class "Default")
      (node (ref "R76") (pin "2") (pinfunction "2_2") (pintype "passive"))
      (node (ref "Z2") (pin "36") (pinfunction "36_36") (pintype "passive"))
    )
    (net (code "31") (name "/ODURX") (class "Default")
      (node (ref "R71") (pin "2") (pinfunction "2_2") (pintype "passive"))
      (node (ref "Z2") (pin "18") (pinfunction "18_18") (pintype "passive"))
    )
    (net (code "32") (name "/ODUTX") (class "Default")
      (node (ref "R72") (pin "1") (pinfunction "1_1") (pintype "passive"))
      (node (ref "Z2") (pin "29") (pinfunction "29_29") (pintype "passive"))
    )
    (net (code "33") (name "/OSHDN") (class "Default")
      (node (ref "R54") (pin "2") (pinfunction "2_2") (pintype "passive"))
      (node (ref "Z2") (pin "12") (pinfunction "12_12") (pintype "passive"))
    )
    (net (code "34") (name "/OWDIN") (class "Default")
      (node (ref "R49") (pin "2") (pinfunction "2_2") (pintype "passive"))
      (node (ref "Z2") (pin "32") (pinfunction "32_32") (pintype "passive"))
    )
    (net (code "35") (name "/PSSDN") (class "Default")
      (node (ref "Q2") (pin "G") (pintype "passive"))
      (node (ref "U8") (pin "2") (pinfunction "PB3/CLKI/ADC3/PINT3_2") (pintype "passive"))
    )
    (net (code "36") (name "/PTTA") (class "Default")
      (node (ref "J12") (pin "1") (pinfunction "1_1") (pintype "passive"))
      (node (ref "Q5") (pin "D") (pintype "passive"))
    )
    (net (code "37") (name "/PTTB") (class "Default")
      (node (ref "J12") (pin "2") (pinfunction "2_2") (pintype "passive"))
      (node (ref "Q6") (pin "D") (pintype "passive"))
    )
    (net (code "38") (name "/PULS") (class "Default")
      (node (ref "J11") (pin "0") (pinfunction "TP_0") (pintype "passive"))
      (node (ref "R52") (pin "2") (pinfunction "2_2") (pintype "passive"))
    )
    (net (code "39") (name "/PWM0") (class "Default")
      (node (ref "J18") (pin "0") (pinfunction "TP_0") (pintype "passive"))
      (node (ref "Z2") (pin "33") (pinfunction "33_33") (pintype "passive"))
    )
    (net (code "40") (name "/R1IN") (class "Default")
      (node (ref "J7") (pin "4") (pinfunction "4_4") (pintype "passive"))
      (node (ref "U3") (pin "13") (pinfunction "R1_IN_13") (pintype "input"))
    )
    (net (code "41") (name "/R2IN") (class "Default")
      (node (ref "J7") (pin "3") (pinfunction "3_3") (pintype "passive"))
      (node (ref "U3") (pin "8") (pinfunction "R2_IN_8") (pintype "input"))
    )
    (net (code "42") (name "/R2OUT") (class "Default")
      (node (ref "J7") (pin "5") (pinfunction "5_5") (pintype "passive"))
      (node (ref "U3") (pin "9") (pinfunction "R2_OUT_9") (pintype "output"))
    )
    (net (code "43") (name "/RFENV") (class "Default")
      (node (ref "C7") (pin "2") (pintype "passive"))
      (node (ref "R10") (pin "1") (pinfunction "1_1") (pintype "passive"))
      (node (ref "R9") (pin "1") (pinfunction "1_1") (pintype "passive"))
      (node (ref "U1") (pin "2") (pinfunction "IN+_2") (pintype "passive"))
      (node (ref "Z2") (pin "37") (pinfunction "37_37") (pintype "passive"))
    )
    (net (code "44") (name "/RFIN") (class "Default")
      (node (ref "C2") (pin "1") (pintype "passive"))
      (node (ref "J4") (pin "2") (pintype "passive"))
      (node (ref "R3") (pin "1") (pinfunction "1_1") (pintype "passive"))
    )
    (net (code "45") (name "/RTS") (class "Default")
      (node (ref "Q7") (pin "D") (pintype "passive"))
      (node (ref "R73") (pin "1") (pinfunction "1_1") (pintype "passive"))
      (node (ref "R84") (pin "2") (pinfunction "2_2") (pintype "passive"))
    )
    (net (code "46") (name "/RTSB") (class "Default")
      (node (ref "Q8") (pin "D") (pintype "passive"))
      (node (ref "R78") (pin "1") (pinfunction "1_1") (pintype "passive"))
      (node (ref "R89") (pin "2") (pinfunction "2_2") (pintype "passive"))
    )
    (net (code "47") (name "/RTSN") (class "Default")
      (node (ref "Q7") (pin "G") (pintype "passive"))
      (node (ref "R83") (pin "2") (pinfunction "2_2") (pintype "passive"))
      (node (ref "U9") (pin "2") (pinfunction "RTS#_2") (pintype "output"))
    )
    (net (code "48") (name "/RXL") (class "Default")
      (node (ref "J9") (pin "5") (pinfunction "5_5") (pintype "passive"))
      (node (ref "R25") (pin "2") (pinfunction "2_2") (pintype "passive"))
    )
    (net (code "49") (name "/RXR") (class "Default")
      (node (ref "J9") (pin "4") (pinfunction "4_4") (pintype "passive"))
      (node (ref "R34") (pin "2") (pinfunction "2_2") (pintype "passive"))
    )
    (net (code "50") (name "/SCL") (class "Default")
      (node (ref "J15") (pin "0") (pinfunction "TP_0") (pintype "passive"))
      (node (ref "R70") (pin "2") (pinfunction "2_2") (pintype "passive"))
    )
    (net (code "51") (name "/SDA") (class "Default")
      (node (ref "J14") (pin "0") (pinfunction "TP_0") (pintype "passive"))
      (node (ref "R69") (pin "2") (pinfunction "2_2") (pintype "passive"))
    )
    (net (code "52") (name "/SFB") (class "Default")
      (node (ref "C13") (pin "2") (pintype "passive"))
      (node (ref "R14") (pin "1") (pinfunction "1_1") (pintype "passive"))
      (node (ref "R15") (pin "2") (pinfunction "2_2") (pintype "passive"))
      (node (ref "U2") (pin "2") (pinfunction "FB_2") (pintype "passive"))
    )
    (net (code "53") (name "/SHDN") (class "Default")
      (node (ref "R53") (pin "2") (pinfunction "2_2") (pintype "passive"))
      (node (ref "R54") (pin "1") (pinfunction "1_1") (pintype "passive"))
      (node (ref "R57") (pin "2") (pinfunction "2_2") (pintype "passive"))
    )
    (net (code "54") (name "/SSW") (class "Default")
      (node (ref "D7") (pin "K") (pinfunction "CATHODE_K") (pintype "passive"))
      (node (ref "L2") (pin "1") (pintype "passive"))
      (node (ref "U2") (pin "0") (pinfunction "SW_0") (pintype "passive"))
      (node (ref "U2") (pin "3") (pinfunction "SW_3") (pintype "passive"))
    )
    (net (code "55") (name "/SV") (class "Default")
      (node (ref "C10") (pin "1") (pintype "passive"))
      (node (ref "C11") (pin "1") (pintype "passive"))
      (node (ref "C4") (pin "1") (pintype "passive"))
      (node (ref "C8") (pin "1") (pinfunction "1_1") (pintype "passive"))
      (node (ref "C9") (pin "1") (pintype "passive"))
      (node (ref "D6") (pin "K") (pinfunction "CATHODE_K") (pintype "passive"))
      (node (ref "L1") (pin "2") (pintype "passive"))
      (node (ref "R13") (pin "2") (pinfunction "2_2") (pintype "passive"))
      (node (ref "U2") (pin "5") (pinfunction "VIN_5") (pintype "passive"))
    )
    (net (code "56") (name "/T2IN") (class "Default")
      (node (ref "J7") (pin "6") (pinfunction "6_6") (pintype "passive"))
      (node (ref "U3") (pin "10") (pinfunction "T2_IN_10") (pintype "input"))
    )
    (net (code "57") (name "/T2OUT") (class "Default")
      (node (ref "J7") (pin "1") (pinfunction "1_1") (pintype "passive"))
      (node (ref "U3") (pin "7") (pinfunction "T2_OUT_7") (pintype "output"))
    )
    (net (code "58") (name "/TIOUT") (class "Default")
      (node (ref "J7") (pin "2") (pinfunction "2_2") (pintype "passive"))
      (node (ref "U3") (pin "14") (pinfunction "T1_OUT_14") (pintype "output"))
    )
    (net (code "59") (name "/TXL") (class "Default")
      (node (ref "C24") (pin "1") (pintype "passive"))
      (node (ref "J9") (pin "3") (pinfunction "3_3") (pintype "passive"))
      (node (ref "R22") (pin "1") (pinfunction "1_1") (pintype "passive"))
    )
    (net (code "60") (name "/TXR") (class "Default")
      (node (ref "C23") (pin "1") (pintype "passive"))
      (node (ref "J9") (pin "2") (pinfunction "2_2") (pintype "passive"))
      (node (ref "R21") (pin "1") (pinfunction "1_1") (pintype "passive"))
    )
    (net (code "61") (name "/UORX") (class "Default")
      (node (ref "J16") (pin "0") (pinfunction "TP_0") (pintype "passive"))
      (node (ref "R71") (pin "1") (pinfunction "1_1") (pintype "passive"))
    )
    (net (code "62") (name "/UOTX") (class "Default")
      (node (ref "J17") (pin "0") (pinfunction "TP_0") (pintype "passive"))
      (node (ref "R72") (pin "2") (pinfunction "2_2") (pintype "passive"))
    )
    (net (code "63") (name "/USCL") (class "Default")
      (node (ref "R70") (pin "1") (pinfunction "1_1") (pintype "passive"))
      (node (ref "Z2") (pin "5") (pinfunction "5_5") (pintype "passive"))
    )
    (net (code "64") (name "/USDA") (class "Default")
      (node (ref "R69") (pin "1") (pinfunction "1_1") (pintype "passive"))
      (node (ref "Z2") (pin "3") (pinfunction "3_3") (pintype "passive"))
    )
    (net (code "65") (name "/VBUSA") (class "Default")
      (node (ref "J20") (pin "VBUS") (pinfunction "VBUS_VBUS") (pintype "passive+no_connect"))
    )
    (net (code "66") (name "/VIND") (class "Default")
      (node (ref "C1") (pin "1") (pintype "passive"))
      (node (ref "D2") (pin "A") (pinfunction "ANODE_A") (pintype "passive"))
      (node (ref "D4") (pin "A") (pinfunction "ANODE_A") (pintype "passive"))
      (node (ref "J2") (pin "1") (pinfunction "1_1") (pintype "passive"))
      (node (ref "R1") (pin "1") (pinfunction "1_1") (pintype "passive"))
      (node (ref "R12") (pin "1") (pinfunction "1_1") (pintype "passive"))
      (node (ref "R2") (pin "1") (pinfunction "1_1") (pintype "passive"))
    )
    (net (code "67") (name "/VINS") (class "Default")
      (node (ref "C5") (pin "1") (pintype "passive"))
      (node (ref "R1") (pin "2") (pinfunction "2_2") (pintype "passive"))
      (node (ref "R4") (pin "2") (pinfunction "2_2") (pintype "passive"))
      (node (ref "R7") (pin "2") (pinfunction "2_2") (pintype "passive"))
      (node (ref "Z2") (pin "40") (pinfunction "40_40") (pintype "passive"))
    )
    (net (code "68") (name "/VMON") (class "Default")
      (node (ref "C6") (pin "1") (pintype "passive"))
      (node (ref "R2") (pin "2") (pinfunction "2_2") (pintype "passive"))
      (node (ref "R5") (pin "2") (pinfunction "2_2") (pintype "passive"))
      (node (ref "R8") (pin "2") (pinfunction "2_2") (pintype "passive"))
      (node (ref "U8") (pin "3") (pinfunction "PB4/ADC2/PINT4_3") (pintype "passive"))
    )
    (net (code "69") (name "/WDIN") (class "Default")
      (node (ref "R46") (pin "2") (pinfunction "2_2") (pintype "passive"))
      (node (ref "R49") (pin "1") (pinfunction "1_1") (pintype "passive"))
      (node (ref "R50") (pin "2") (pinfunction "2_2") (pintype "passive"))
    )
    (net (code "70") (name "/WDOUT") (class "Default")
      (node (ref "R59") (pin "2") (pinfunction "2_2") (pintype "passive"))
      (node (ref "Z2") (pin "31") (pinfunction "31_31") (pintype "passive"))
    )
    (net (code "71") (name "3V3") (class "Default")
      (node (ref "C12") (pin "1") (pintype "passive"))
      (node (ref "C15") (pin "1") (pintype "passive"))
      (node (ref "C34") (pin "1") (pintype "passive"))
      (node (ref "C39") (pin "2") (pintype "passive"))
      (node (ref "C40") (pin "1") (pintype "passive"))
      (node (ref "D9") (pin "A") (pintype "passive"))
      (node (ref "R23") (pin "1") (pinfunction "1_1") (pintype "passive"))
      (node (ref "R40") (pin "1") (pinfunction "1_1") (pintype "passive"))
      (node (ref "R42") (pin "1") (pinfunction "1_1") (pintype "passive"))
      (node (ref "R47") (pin "1") (pinfunction "1_1") (pintype "passive"))
      (node (ref "R48") (pin "1") (pinfunction "1_1") (pintype "passive"))
      (node (ref "R55") (pin "1") (pinfunction "1_1") (pintype "passive"))
      (node (ref "R56") (pin "1") (pinfunction "1_1") (pintype "passive"))
      (node (ref "R66") (pin "1") (pinfunction "1_1") (pintype "passive"))
      (node (ref "U1") (pin "1") (pinfunction "VREF_1") (pintype "passive"))
      (node (ref "U1") (pin "8") (pinfunction "VDD_8") (pintype "passive"))
      (node (ref "U3") (pin "16") (pinfunction "3V3_16") (pintype "passive"))
      (node (ref "U5") (pin "8") (pinfunction "VDD_8") (pintype "power_in"))
      (node (ref "U6") (pin "2") (pinfunction "VOUT_2") (pintype "passive"))
      (node (ref "U6") (pin "4") (pinfunction "VOUTTAB_4") (pintype "passive"))
      (node (ref "U8") (pin "8") (pinfunction "VCC_8") (pintype "passive"))
    )
    (net (code "72") (name "5V") (class "Default")
      (node (ref "C13") (pin "1") (pintype "passive"))
      (node (ref "C14") (pin "1") (pintype "passive"))
      (node (ref "C16") (pin "1") (pintype "passive"))
      (node (ref "C17") (pin "1") (pintype "passive"))
      (node (ref "C18") (pin "1") (pinfunction "1_1") (pintype "passive"))
      (node (ref "C26") (pin "1") (pintype "passive"))
      (node (ref "C33") (pin "1") (pintype "passive"))
      (node (ref "C49") (pin "1") (pintype "passive"))
      (node (ref "C57") (pin "1") (pintype "passive"))
      (node (ref "D8") (pin "K") (pinfunction "CATHODE_K") (pintype "passive"))
      (node (ref "L2") (pin "2") (pintype "passive"))
      (node (ref "Q1") (pin "S") (pintype "passive"))
      (node (ref "R16") (pin "1") (pinfunction "1_1") (pintype "passive"))
      (node (ref "R20") (pin "1") (pinfunction "1_1") (pintype "passive"))
      (node (ref "R36") (pin "1") (pinfunction "1_1") (pintype "passive"))
      (node (ref "R39") (pin "1") (pinfunction "1_1") (pintype "passive"))
      (node (ref "R60") (pin "2") (pinfunction "2_2") (pintype "passive"))
      (node (ref "R64") (pin "2") (pinfunction "2_2") (pintype "passive"))
      (node (ref "R65") (pin "2") (pinfunction "2_2") (pintype "passive"))
      (node (ref "R84") (pin "1") (pinfunction "1_1") (pintype "passive"))
      (node (ref "R89") (pin "1") (pinfunction "1_1") (pintype "passive"))
      (node (ref "U6") (pin "3") (pinfunction "VIN_3") (pintype "passive"))
      (node (ref "U9") (pin "12") (pinfunction "VCC_12") (pintype "passive"))
    )
    (net (code "73") (name "GND") (class "Default")
      (node (ref "C1") (pin "2") (pintype "passive"))
      (node (ref "C10") (pin "2") (pintype "passive"))
      (node (ref "C12") (pin "2") (pintype "passive"))
      (node (ref "C14") (pin "2") (pintype "passive"))
      (node (ref "C15") (pin "2") (pintype "passive"))
      (node (ref "C16") (pin "2") (pintype "passive"))
      (node (ref "C17") (pin "2") (pintype "passive"))
      (node (ref "C18") (pin "2") (pinfunction "2_2") (pintype "passive"))
      (node (ref "C19") (pin "1") (pintype "passive"))
      (node (ref "C20") (pin "1") (pintype "passive"))
      (node (ref "C23") (pin "2") (pintype "passive"))
      (node (ref "C24") (pin "2") (pintype "passive"))
      (node (ref "C25") (pin "2") (pintype "passive"))
      (node (ref "C26") (pin "2") (pintype "passive"))
      (node (ref "C28") (pin "1") (pintype "passive"))
      (node (ref "C29") (pin "2") (pintype "passive"))
      (node (ref "C3") (pin "2") (pintype "passive"))
      (node (ref "C30") (pin "1") (pintype "passive"))
      (node (ref "C31") (pin "2") (pintype "passive"))
      (node (ref "C32") (pin "2") (pintype "passive"))
      (node (ref "C33") (pin "2") (pintype "passive"))
      (node (ref "C34") (pin "2") (pintype "passive"))
      (node (ref "C35") (pin "2") (pintype "passive"))
      (node (ref "C37") (pin "2") (pintype "passive"))
      (node (ref "C38") (pin "2") (pintype "passive"))
      (node (ref "C39") (pin "1") (pintype "passive"))
      (node (ref "C4") (pin "2") (pintype "passive"))
      (node (ref "C40") (pin "2") (pintype "passive"))
      (node (ref "C41") (pin "2") (pintype "passive"))
      (node (ref "C42") (pin "2") (pintype "passive"))
      (node (ref "C43") (pin "2") (pintype "passive"))
      (node (ref "C44") (pin "1") (pintype "passive"))
      (node (ref "C45") (pin "2") (pintype "passive"))
      (node (ref "C46") (pin "1") (pintype "passive"))
      (node (ref "C47") (pin "1") (pintype "passive"))
      (node (ref "C48") (pin "2") (pintype "passive"))
      (node (ref "C49") (pin "2") (pintype "passive"))
      (node (ref "C5") (pin "2") (pintype "passive"))
      (node (ref "C50") (pin "2") (pintype "passive"))
      (node (ref "C51") (pin "2") (pintype "passive"))
      (node (ref "C52") (pin "2") (pintype "passive"))
      (node (ref "C53") (pin "2") (pintype "passive"))
      (node (ref "C54") (pin "2") (pintype "passive"))
      (node (ref "C55") (pin "1") (pintype "passive"))
      (node (ref "C56") (pin "1") (pintype "passive"))
      (node (ref "C57") (pin "2") (pintype "passive"))
      (node (ref "C6") (pin "2") (pintype "passive"))
      (node (ref "C7") (pin "1") (pintype "passive"))
      (node (ref "C8") (pin "2") (pinfunction "2_2") (pintype "passive"))
      (node (ref "C9") (pin "2") (pintype "passive"))
      (node (ref "D10") (pin "K") (pintype "passive"))
      (node (ref "D3") (pin "2") (pinfunction "K2_2") (pintype "passive"))
      (node (ref "D5") (pin "K") (pintype "passive"))
      (node (ref "D6") (pin "A") (pinfunction "ANODE_A") (pintype "passive"))
      (node (ref "D7") (pin "A") (pinfunction "ANODE_A") (pintype "passive"))
      (node (ref "D8") (pin "A") (pinfunction "ANODE_A") (pintype "passive"))
      (node (ref "J10") (pin "1") (pinfunction "1_1") (pintype "passive"))
      (node (ref "J19") (pin "4") (pinfunction "GND_4") (pintype "passive"))
      (node (ref "J19") (pin "5") (pinfunction "FRM_5") (pintype "passive"))
      (node (ref "J19") (pin "6") (pinfunction "FRM_6") (pintype "passive"))
      (node (ref "J2") (pin "4") (pinfunction "4_4") (pintype "passive"))
      (node (ref "J20") (pin "BODY") (pinfunction "BODY_BODY") (pintype "passive"))
      (node (ref "J20") (pin "GND") (pinfunction "GND_GND") (pintype "passive"))
      (node (ref "J4") (pin "1") (pintype "passive"))
      (node (ref "J9") (pin "1") (pinfunction "1_1") (pintype "passive"))
      (node (ref "Q2") (pin "S") (pintype "passive"))
      (node (ref "Q5") (pin "S") (pintype "passive"))
      (node (ref "Q6") (pin "S") (pintype "passive"))
      (node (ref "Q7") (pin "S") (pintype "passive"))
      (node (ref "Q8") (pin "S") (pintype "passive"))
      (node (ref "R14") (pin "2") (pinfunction "2_2") (pintype "passive"))
      (node (ref "R24") (pin "2") (pinfunction "2_2") (pintype "passive"))
      (node (ref "R26") (pin "1") (pinfunction "1_1") (pintype "passive"))
      (node (ref "R27") (pin "1") (pinfunction "1_1") (pintype "passive"))
      (node (ref "R28") (pin "1") (pinfunction "1_1") (pintype "passive"))
      (node (ref "R29") (pin "1") (pinfunction "1_1") (pintype "passive"))
      (node (ref "R3") (pin "2") (pinfunction "2_2") (pintype "passive"))
      (node (ref "R30") (pin "1") (pinfunction "1_1") (pintype "passive"))
      (node (ref "R35") (pin "2") (pinfunction "2_2") (pintype "passive"))
      (node (ref "R4") (pin "1") (pinfunction "1_1") (pintype "passive"))
      (node (ref "R41") (pin "2") (pinfunction "2_2") (pintype "passive"))
      (node (ref "R43") (pin "2") (pinfunction "2_2") (pintype "passive"))
      (node (ref "R45") (pin "2") (pinfunction "2_2") (pintype "passive"))
      (node (ref "R5") (pin "1") (pinfunction "1_1") (pintype "passive"))
      (node (ref "R51") (pin "2") (pinfunction "2_2") (pintype "passive"))
      (node (ref "R58") (pin "2") (pinfunction "2_2") (pintype "passive"))
      (node (ref "R6") (pin "2") (pinfunction "2_2") (pintype "passive"))
      (node (ref "R67") (pin "2") (pinfunction "2_2") (pintype "passive"))
      (node (ref "R7") (pin "1") (pinfunction "1_1") (pintype "passive"))
      (node (ref "R75") (pin "2") (pinfunction "2_2") (pintype "passive"))
      (node (ref "R77") (pin "2") (pinfunction "2_2") (pintype "passive"))
      (node (ref "R8") (pin "1") (pinfunction "1_1") (pintype "passive"))
      (node (ref "R83") (pin "1") (pinfunction "1_1") (pintype "passive"))
      (node (ref "R87") (pin "1") (pinfunction "1_1") (pintype "passive"))
      (node (ref "R88") (pin "2") (pinfunction "2_2") (pintype "passive"))
      (node (ref "R9") (pin "2") (pinfunction "2_2") (pintype "passive"))
      (node (ref "U1") (pin "3") (pinfunction "IN-_3") (pintype "passive"))
      (node (ref "U1") (pin "4") (pinfunction "VSS_4") (pintype "passive"))
      (node (ref "U2") (pin "1") (pinfunction "GND_1") (pintype "passive"))
      (node (ref "U3") (pin "15") (pinfunction "GND_15") (pintype "passive"))
      (node (ref "U4") (pin "7") (pinfunction "1E_7") (pintype "passive"))
      (node (ref "U5") (pin "4") (pinfunction "VSS_4") (pintype "power_in"))
      (node (ref "U5") (pin "7") (pinfunction "WP_7") (pintype "input"))
      (node (ref "U6") (pin "1") (pinfunction "GNDADJ_1") (pintype "passive"))
      (node (ref "U7") (pin "14") (pinfunction "AGND_14") (pintype "passive"))
      (node (ref "U7") (pin "21") (pinfunction "AGND_21") (pintype "passive"))
      (node (ref "U7") (pin "27") (pinfunction "AGND_27") (pintype "passive"))
      (node (ref "U7") (pin "40") (pinfunction "GND3IO_40") (pintype "passive"))
      (node (ref "U7") (pin "8") (pinfunction "GND18_8") (pintype "passive"))
      (node (ref "U8") (pin "4") (pinfunction "GND_4") (pintype "passive"))
      (node (ref "U9") (pin "13") (pinfunction "GND_13") (pintype "passive"))
      (node (ref "U9") (pin "5") (pinfunction "GND_5") (pintype "passive"))
      (node (ref "Z1") (pin "0") (pinfunction "GND_0") (pintype "passive"))
      (node (ref "Z2") (pin "34") (pinfunction "34_34") (pintype "passive"))
      (node (ref "Z2") (pin "39") (pinfunction "39_39") (pintype "passive"))
      (node (ref "Z2") (pin "6") (pinfunction "6_6") (pintype "passive"))
      (node (ref "Z2") (pin "9") (pinfunction "9_9") (pintype "passive"))
      (node (ref "Z3") (pin "3") (pinfunction "BLACK_3") (pintype "passive"))
    )
    (net (code "74") (name "Net-(C25-Pad1)") (class "Default")
      (node (ref "C25") (pin "1") (pintype "passive"))
      (node (ref "R32") (pin "2") (pinfunction "2_2") (pintype "passive"))
      (node (ref "R33") (pin "1") (pinfunction "1_1") (pintype "passive"))
    )
    (net (code "75") (name "Net-(C27-Pad1)") (class "Default")
      (node (ref "C27") (pin "1") (pintype "passive"))
      (node (ref "L6") (pin "2") (pintype "passive"))
      (node (ref "R33") (pin "2") (pinfunction "2_2") (pintype "passive"))
    )
    (net (code "76") (name "Net-(C27-Pad2)") (class "Default")
      (node (ref "C27") (pin "2") (pintype "passive"))
      (node (ref "R24") (pin "1") (pinfunction "1_1") (pintype "passive"))
      (node (ref "R25") (pin "1") (pinfunction "1_1") (pintype "passive"))
    )
    (net (code "77") (name "Net-(C35-Pad1)") (class "Default")
      (node (ref "C35") (pin "1") (pintype "passive"))
      (node (ref "R37") (pin "1") (pinfunction "1_1") (pintype "passive"))
      (node (ref "R44") (pin "2") (pinfunction "2_2") (pintype "passive"))
    )
    (net (code "78") (name "Net-(C36-Pad1)") (class "Default")
      (node (ref "C36") (pin "1") (pintype "passive"))
      (node (ref "L7") (pin "2") (pintype "passive"))
      (node (ref "R37") (pin "2") (pinfunction "2_2") (pintype "passive"))
    )
    (net (code "79") (name "Net-(C36-Pad2)") (class "Default")
      (node (ref "C36") (pin "2") (pintype "passive"))
      (node (ref "R34") (pin "1") (pinfunction "1_1") (pintype "passive"))
      (node (ref "R45") (pin "1") (pinfunction "1_1") (pintype "passive"))
    )
    (net (code "80") (name "Net-(D1-CATHODE)") (class "Default")
      (node (ref "D1") (pin "K") (pinfunction "CATHODE_K") (pintype "passive"))
      (node (ref "D2") (pin "K") (pinfunction "CATHODE_K") (pintype "passive"))
      (node (ref "L1") (pin "1") (pintype "passive"))
    )
    (net (code "81") (name "Net-(D3-B)") (class "Default")
      (node (ref "C2") (pin "2") (pintype "passive"))
      (node (ref "D3") (pin "3") (pinfunction "B_3") (pintype "passive"))
    )
    (net (code "82") (name "Net-(D3-K1)") (class "Default")
      (node (ref "C3") (pin "1") (pintype "passive"))
      (node (ref "D3") (pin "1") (pinfunction "K1_1") (pintype "passive"))
      (node (ref "R10") (pin "2") (pinfunction "2_2") (pintype "passive"))
      (node (ref "R6") (pin "1") (pinfunction "1_1") (pintype "passive"))
    )
    (net (code "83") (name "Net-(D5-PadA)") (class "Default")
      (node (ref "D5") (pin "A") (pintype "passive"))
      (node (ref "R11") (pin "2") (pinfunction "2_2") (pintype "passive"))
    )
    (net (code "84") (name "Net-(D9-PadK)") (class "Default")
      (node (ref "D9") (pin "K") (pintype "passive"))
      (node (ref "R31") (pin "1") (pinfunction "1_1") (pintype "passive"))
    )
    (net (code "85") (name "Net-(D10-PadA)") (class "Default")
      (node (ref "D10") (pin "A") (pintype "passive"))
      (node (ref "R36") (pin "2") (pinfunction "2_2") (pintype "passive"))
    )
    (net (code "86") (name "Net-(J1-Pad1)") (class "Default")
      (node (ref "J1") (pin "1") (pinfunction "1_1") (pintype "passive"))
      (node (ref "J5") (pin "1") (pinfunction "1_1") (pintype "passive"))
    )
    (net (code "87") (name "Net-(J1-Pad2)") (class "Default")
      (node (ref "J1") (pin "2") (pinfunction "2_2") (pintype "passive"))
      (node (ref "J5") (pin "2") (pinfunction "2_2") (pintype "passive"))
    )
    (net (code "88") (name "Net-(J1-Pad3)") (class "Default")
      (node (ref "J1") (pin "3") (pinfunction "3_3") (pintype "passive"))
      (node (ref "J5") (pin "3") (pinfunction "3_3") (pintype "passive"))
    )
    (net (code "89") (name "Net-(J1-Pad4)") (class "Default")
      (node (ref "J1") (pin "4") (pinfunction "4_4") (pintype "passive"))
      (node (ref "J5") (pin "4") (pinfunction "4_4") (pintype "passive"))
    )
    (net (code "90") (name "Net-(J1-Pad5)") (class "Default")
      (node (ref "J1") (pin "5") (pinfunction "5_5") (pintype "passive"))
      (node (ref "J5") (pin "5") (pinfunction "5_5") (pintype "passive"))
    )
    (net (code "91") (name "Net-(J1-Pad6)") (class "Default")
      (node (ref "J1") (pin "6") (pinfunction "6_6") (pintype "passive"))
      (node (ref "J5") (pin "6") (pinfunction "6_6") (pintype "passive"))
    )
    (net (code "92") (name "Net-(J3-Pad1)") (class "Default")
      (node (ref "J3") (pin "1") (pinfunction "1_1") (pintype "passive"))
      (node (ref "J6") (pin "1") (pinfunction "1_1") (pintype "passive"))
    )
    (net (code "93") (name "Net-(J3-Pad2)") (class "Default")
      (node (ref "J3") (pin "2") (pinfunction "2_2") (pintype "passive"))
      (node (ref "J6") (pin "2") (pinfunction "2_2") (pintype "passive"))
    )
    (net (code "94") (name "Net-(J3-Pad3)") (class "Default")
      (node (ref "J3") (pin "3") (pinfunction "3_3") (pintype "passive"))
      (node (ref "J6") (pin "3") (pinfunction "3_3") (pintype "passive"))
    )
    (net (code "95") (name "Net-(J3-Pad4)") (class "Default")
      (node (ref "J3") (pin "4") (pinfunction "4_4") (pintype "passive"))
      (node (ref "J6") (pin "4") (pinfunction "4_4") (pintype "passive"))
    )
    (net (code "96") (name "Net-(J3-Pad5)") (class "Default")
      (node (ref "J3") (pin "5") (pinfunction "5_5") (pintype "passive"))
      (node (ref "J6") (pin "5") (pinfunction "5_5") (pintype "passive"))
    )
    (net (code "97") (name "Net-(J3-Pad6)") (class "Default")
      (node (ref "J3") (pin "6") (pinfunction "6_6") (pintype "passive"))
      (node (ref "J6") (pin "6") (pinfunction "6_6") (pintype "passive"))
    )
    (net (code "98") (name "Net-(J3-Pad7)") (class "Default")
      (node (ref "J3") (pin "7") (pinfunction "7_7") (pintype "passive"))
      (node (ref "J6") (pin "7") (pinfunction "7_7") (pintype "passive"))
    )
    (net (code "99") (name "Net-(J3-Pad8)") (class "Default")
      (node (ref "J3") (pin "8") (pinfunction "8_8") (pintype "passive"))
      (node (ref "J6") (pin "8") (pinfunction "8_8") (pintype "passive"))
    )
    (net (code "100") (name "Net-(J19-VCC)") (class "Default")
      (node (ref "J19") (pin "1") (pinfunction "VCC_1") (pintype "passive"))
      (node (ref "R90") (pin "1") (pinfunction "1_1") (pintype "passive"))
    )
    (net (code "101") (name "Net-(L3-Pad2)") (class "Default")
      (node (ref "L3") (pin "2") (pintype "passive"))
      (node (ref "R20") (pin "2") (pinfunction "2_2") (pintype "passive"))
    )
    (net (code "102") (name "Net-(L4-Pad2)") (class "Default")
      (node (ref "L4") (pin "2") (pintype "passive"))
      (node (ref "R21") (pin "2") (pinfunction "2_2") (pintype "passive"))
    )
    (net (code "103") (name "Net-(L5-Pad2)") (class "Default")
      (node (ref "L5") (pin "2") (pintype "passive"))
      (node (ref "R22") (pin "2") (pinfunction "2_2") (pintype "passive"))
    )
    (net (code "104") (name "Net-(L8-Pad1)") (class "Default")
      (node (ref "L8") (pin "1") (pintype "passive"))
      (node (ref "R60") (pin "1") (pinfunction "1_1") (pintype "passive"))
    )
    (net (code "105") (name "Net-(L9-Pad1)") (class "Default")
      (node (ref "L9") (pin "1") (pintype "passive"))
      (node (ref "R64") (pin "1") (pinfunction "1_1") (pintype "passive"))
      (node (ref "R65") (pin "1") (pinfunction "1_1") (pintype "passive"))
    )
    (net (code "106") (name "Net-(Q1-PadG)") (class "Default")
      (node (ref "Q1") (pin "G") (pintype "passive"))
      (node (ref "R38") (pin "1") (pinfunction "1_1") (pintype "passive"))
      (node (ref "R39") (pin "2") (pinfunction "2_2") (pintype "passive"))
    )
    (net (code "107") (name "Net-(Q2-PadD)") (class "Default")
      (node (ref "Q2") (pin "D") (pintype "passive"))
      (node (ref "R38") (pin "2") (pinfunction "2_2") (pintype "passive"))
      (node (ref "R41") (pin "1") (pinfunction "1_1") (pintype "passive"))
    )
    (net (code "108") (name "Net-(Q3-PadD)") (class "Default")
      (node (ref "Q3") (pin "D") (pintype "passive"))
      (node (ref "R56") (pin "2") (pinfunction "2_2") (pintype "passive"))
      (node (ref "R61") (pin "2") (pinfunction "2_2") (pintype "passive"))
    )
    (net (code "109") (name "Net-(Q3-PadG)") (class "Default")
      (node (ref "Q3") (pin "G") (pintype "passive"))
      (node (ref "R51") (pin "1") (pinfunction "1_1") (pintype "passive"))
      (node (ref "R52") (pin "1") (pinfunction "1_1") (pintype "passive"))
    )
    (net (code "110") (name "Net-(Q3-PadS)") (class "Default")
      (node (ref "Q3") (pin "S") (pintype "passive"))
      (node (ref "Q4") (pin "S") (pintype "passive"))
      (node (ref "R58") (pin "1") (pinfunction "1_1") (pintype "passive"))
    )
    (net (code "111") (name "Net-(Q4-PadG)") (class "Default")
      (node (ref "Q4") (pin "G") (pintype "passive"))
      (node (ref "R61") (pin "1") (pinfunction "1_1") (pintype "passive"))
      (node (ref "R67") (pin "1") (pinfunction "1_1") (pintype "passive"))
    )
    (net (code "112") (name "Net-(Q5-PadG)") (class "Default")
      (node (ref "Q5") (pin "G") (pintype "passive"))
      (node (ref "R73") (pin "2") (pinfunction "2_2") (pintype "passive"))
      (node (ref "R74") (pin "1") (pinfunction "1_1") (pintype "passive"))
      (node (ref "R75") (pin "1") (pinfunction "1_1") (pintype "passive"))
    )
    (net (code "113") (name "Net-(Q6-PadG)") (class "Default")
      (node (ref "Q6") (pin "G") (pintype "passive"))
      (node (ref "R76") (pin "1") (pinfunction "1_1") (pintype "passive"))
      (node (ref "R77") (pin "1") (pinfunction "1_1") (pintype "passive"))
      (node (ref "R78") (pin "2") (pinfunction "2_2") (pintype "passive"))
    )
    (net (code "114") (name "Net-(R11-Pad1)") (class "Default")
      (node (ref "R11") (pin "1") (pinfunction "1_1") (pintype "passive"))
      (node (ref "R12") (pin "2") (pinfunction "2_2") (pintype "passive"))
    )
    (net (code "115") (name "Net-(R15-Pad1)") (class "Default")
      (node (ref "R15") (pin "1") (pinfunction "1_1") (pintype "passive"))
      (node (ref "R16") (pin "2") (pinfunction "2_2") (pintype "passive"))
    )
    (net (code "116") (name "Net-(U2-VC)") (class "Default")
      (node (ref "C11") (pin "2") (pintype "passive"))
      (node (ref "R13") (pin "1") (pinfunction "1_1") (pintype "passive"))
      (node (ref "U2") (pin "4") (pinfunction "VC_4") (pintype "passive"))
    )
    (net (code "117") (name "Net-(U3-C1+)") (class "Default")
      (node (ref "C22") (pin "1") (pintype "passive"))
      (node (ref "U3") (pin "1") (pinfunction "C1+_1") (pintype "passive"))
    )
    (net (code "118") (name "Net-(U3-C1_-)") (class "Default")
      (node (ref "C22") (pin "2") (pintype "passive"))
      (node (ref "U3") (pin "3") (pinfunction "C1_-_3") (pintype "passive"))
    )
    (net (code "119") (name "Net-(U3-C2+)") (class "Default")
      (node (ref "C21") (pin "1") (pintype "passive"))
      (node (ref "U3") (pin "4") (pinfunction "C2+_4") (pintype "passive"))
    )
    (net (code "120") (name "Net-(U3-C2_-)") (class "Default")
      (node (ref "C21") (pin "2") (pintype "passive"))
      (node (ref "U3") (pin "5") (pinfunction "C2_-_5") (pintype "passive"))
    )
    (net (code "121") (name "Net-(U3-V+)") (class "Default")
      (node (ref "C19") (pin "2") (pintype "passive"))
      (node (ref "U3") (pin "2") (pinfunction "V+_2") (pintype "passive"))
    )
    (net (code "122") (name "Net-(U3-V-)") (class "Default")
      (node (ref "C20") (pin "2") (pintype "passive"))
      (node (ref "U3") (pin "6") (pinfunction "V-_6") (pintype "passive"))
    )
    (net (code "123") (name "Net-(U4-1A)") (class "Default")
      (node (ref "R17") (pin "2") (pinfunction "2_2") (pintype "passive"))
      (node (ref "U4") (pin "1") (pinfunction "1A_1") (pintype "passive"))
    )
    (net (code "124") (name "Net-(U4-1C)") (class "Default")
      (node (ref "R18") (pin "1") (pinfunction "1_1") (pintype "passive"))
      (node (ref "U4") (pin "8") (pinfunction "1C_8") (pintype "passive"))
    )
    (net (code "125") (name "Net-(U4-2A)") (class "Default")
      (node (ref "R19") (pin "2") (pinfunction "2_2") (pintype "passive"))
      (node (ref "U4") (pin "3") (pinfunction "2A_3") (pintype "passive"))
    )
    (net (code "126") (name "Net-(U5-A0)") (class "Default")
      (node (ref "R28") (pin "2") (pinfunction "2_2") (pintype "passive"))
      (node (ref "U5") (pin "1") (pinfunction "A0_1") (pintype "input"))
    )
    (net (code "127") (name "Net-(U5-A1)") (class "Default")
      (node (ref "R27") (pin "2") (pinfunction "2_2") (pintype "passive"))
      (node (ref "U5") (pin "2") (pinfunction "A1_2") (pintype "input"))
    )
    (net (code "128") (name "Net-(U5-A2)") (class "Default")
      (node (ref "R26") (pin "2") (pinfunction "2_2") (pintype "passive"))
      (node (ref "U5") (pin "3") (pinfunction "A2_3") (pintype "input"))
    )
    (net (code "129") (name "Net-(U5-SCL)") (class "Default")
      (node (ref "R48") (pin "2") (pinfunction "2_2") (pintype "passive"))
      (node (ref "U5") (pin "6") (pinfunction "SCL_6") (pintype "passive"))
      (node (ref "U7") (pin "46") (pinfunction "SCL_46") (pintype "passive"))
    )
    (net (code "130") (name "Net-(U5-SDA)") (class "Default")
      (node (ref "R47") (pin "2") (pinfunction "2_2") (pintype "passive"))
      (node (ref "U5") (pin "5") (pinfunction "SDA_5") (pintype "passive"))
      (node (ref "U7") (pin "47") (pinfunction "SDA_47") (pintype "passive"))
    )
    (net (code "131") (name "Net-(U7-AAMIXEN)") (class "Default")
      (node (ref "R40") (pin "2") (pinfunction "2_2") (pintype "passive"))
      (node (ref "R43") (pin "1") (pinfunction "1_1") (pintype "passive"))
      (node (ref "U7") (pin "39") (pinfunction "AAMIXEN_39") (pintype "passive"))
    )
    (net (code "132") (name "Net-(U7-AV50)") (class "Default")
      (node (ref "C28") (pin "2") (pintype "passive"))
      (node (ref "C30") (pin "2") (pintype "passive"))
      (node (ref "L3") (pin "1") (pintype "passive"))
      (node (ref "U7") (pin "30") (pinfunction "AV50_30") (pintype "passive"))
    )
    (net (code "133") (name "Net-(U7-DV50)") (class "Default")
      (node (ref "C46") (pin "2") (pintype "passive"))
      (node (ref "C47") (pin "2") (pintype "passive"))
      (node (ref "L8") (pin "2") (pintype "passive"))
      (node (ref "U7") (pin "13") (pinfunction "DV50_13") (pintype "passive"))
    )
    (net (code "134") (name "Net-(U7-GPIO9)") (class "Default")
      (node (ref "R31") (pin "2") (pinfunction "2_2") (pintype "passive"))
      (node (ref "U7") (pin "35") (pinfunction "GPIO9_35") (pintype "passive"))
    )
    (net (code "135") (name "Net-(U7-MODE_0)") (class "Default")
      (node (ref "R29") (pin "2") (pinfunction "2_2") (pintype "passive"))
      (node (ref "U7") (pin "32") (pinfunction "MODE_0_32") (pintype "input"))
    )
    (net (code "136") (name "Net-(U7-MODE_1)") (class "Default")
      (node (ref "R30") (pin "2") (pinfunction "2_2") (pintype "passive"))
      (node (ref "U7") (pin "31") (pinfunction "MODE_1_31") (pintype "input"))
    )
    (net (code "137") (name "Net-(U7-PDSW)") (class "Default")
      (node (ref "R55") (pin "2") (pinfunction "2_2") (pintype "passive"))
      (node (ref "U7") (pin "4") (pinfunction "PDSW_4") (pintype "passive"))
    )
    (net (code "138") (name "Net-(U7-XACREF)") (class "Default")
      (node (ref "C41") (pin "1") (pintype "passive"))
      (node (ref "U7") (pin "15") (pinfunction "XACREF_15") (pintype "passive"))
    )
    (net (code "139") (name "Net-(U7-XLNOUTL)") (class "Default")
      (node (ref "L5") (pin "1") (pintype "passive"))
      (node (ref "U7") (pin "24") (pinfunction "XLNOUTL_24") (pintype "passive"))
    )
    (net (code "140") (name "Net-(U7-XLNOUTR)") (class "Default")
      (node (ref "L4") (pin "1") (pintype "passive"))
      (node (ref "U7") (pin "28") (pinfunction "XLNOUTR_28") (pintype "passive"))
    )
    (net (code "141") (name "Net-(U7-XLOCOM)") (class "Default")
      (node (ref "C32") (pin "1") (pintype "passive"))
      (node (ref "U7") (pin "25") (pinfunction "XLOCOM_25") (pintype "passive"))
    )
    (net (code "142") (name "Net-(U7-XMICBIAS1)") (class "Default")
      (node (ref "R32") (pin "1") (pinfunction "1_1") (pintype "passive"))
      (node (ref "U7") (pin "19") (pinfunction "XMICBIAS1_19") (pintype "passive"))
    )
    (net (code "143") (name "Net-(U7-XMICBIAS2)") (class "Default")
      (node (ref "R44") (pin "1") (pinfunction "1_1") (pintype "passive"))
      (node (ref "U7") (pin "18") (pinfunction "XMICBIAS2_18") (pintype "passive"))
    )
    (net (code "144") (name "Net-(U7-XMICL)") (class "Default")
      (node (ref "C42") (pin "1") (pintype "passive"))
      (node (ref "L6") (pin "1") (pintype "passive"))
      (node (ref "U7") (pin "16") (pinfunction "XMICL_16") (pintype "passive"))
    )
    (net (code "145") (name "Net-(U7-XMICR)") (class "Default")
      (node (ref "C43") (pin "1") (pintype "passive"))
      (node (ref "L7") (pin "1") (pintype "passive"))
      (node (ref "U7") (pin "17") (pinfunction "XMICR_17") (pintype "passive"))
    )
    (net (code "146") (name "Net-(U7-XTAL_I)") (class "Default")
      (node (ref "C44") (pin "2") (pintype "passive"))
      (node (ref "C50") (pin "1") (pintype "passive"))
      (node (ref "R68") (pin "2") (pinfunction "2_2") (pintype "passive"))
      (node (ref "U7") (pin "6") (pinfunction "XTAL_I_6") (pintype "passive"))
      (node (ref "Y1") (pin "1") (pintype "passive"))
    )
    (net (code "147") (name "Net-(U7-XTAL_O)") (class "Default")
      (node (ref "C51") (pin "1") (pintype "passive"))
      (node (ref "R68") (pin "1") (pinfunction "1_1") (pintype "passive"))
      (node (ref "U7") (pin "7") (pinfunction "XTAL_O_7") (pintype "passive"))
      (node (ref "Y1") (pin "2") (pintype "passive"))
    )
    (net (code "148") (name "Net-(U7-XV18)") (class "Default")
      (node (ref "C48") (pin "1") (pintype "passive"))
      (node (ref "U7") (pin "11") (pinfunction "XV18_11") (pintype "passive"))
    )
    (net (code "149") (name "Net-(U7-XV33)") (class "Default")
      (node (ref "C45") (pin "1") (pintype "passive"))
      (node (ref "U7") (pin "12") (pinfunction "XV33_12") (pintype "passive"))
    )
    (net (code "150") (name "Net-(U7-XV35_ADC)") (class "Default")
      (node (ref "C37") (pin "1") (pintype "passive"))
      (node (ref "U7") (pin "22") (pinfunction "XV35_ADC_22") (pintype "passive"))
    )
    (net (code "151") (name "Net-(U7-XV35_DAC)") (class "Default")
      (node (ref "C29") (pin "1") (pintype "passive"))
      (node (ref "U7") (pin "29") (pinfunction "XV35_DAC_29") (pintype "passive"))
    )
    (net (code "152") (name "Net-(U7-XV35_DRIVER)") (class "Default")
      (node (ref "C31") (pin "1") (pintype "passive"))
      (node (ref "U7") (pin "26") (pinfunction "XV35_DRIVER_26") (pintype "passive"))
    )
    (net (code "153") (name "Net-(U7-XVAG)") (class "Default")
      (node (ref "C38") (pin "1") (pintype "passive"))
      (node (ref "U7") (pin "20") (pinfunction "XVAG_20") (pintype "passive"))
    )
    (net (code "154") (name "Net-(U7-XVOLADJ)") (class "Default")
      (node (ref "R23") (pin "2") (pinfunction "2_2") (pintype "passive"))
      (node (ref "R35") (pin "1") (pinfunction "1_1") (pintype "passive"))
      (node (ref "U7") (pin "23") (pinfunction "XVOLADJ_23") (pintype "passive"))
    )
    (net (code "155") (name "Net-(U8-PB0{slash}MOSI{slash}AIN0{slash}OC1A{slash}PINT0)") (class "Default")
      (node (ref "R59") (pin "1") (pinfunction "1_1") (pintype "passive"))
      (node (ref "U8") (pin "5") (pinfunction "PB0/MOSI/AIN0/OC1A/PINT0_5") (pintype "passive"))
    )
    (net (code "156") (name "Net-(U8-PB1{slash}MISO{slash}INT0{slash}AIN1{slash}PINT1)") (class "Default")
      (node (ref "R53") (pin "1") (pinfunction "1_1") (pintype "passive"))
      (node (ref "U8") (pin "6") (pinfunction "PB1/MISO/INT0/AIN1/PINT1_6") (pintype "passive"))
    )
    (net (code "157") (name "Net-(U8-PB2{slash}SCK{slash}T0{slash}ADC1{slash}PINT2)") (class "Default")
      (node (ref "R50") (pin "1") (pinfunction "1_1") (pintype "passive"))
      (node (ref "U8") (pin "7") (pinfunction "PB2/SCK/T0/ADC1/PINT2_7") (pintype "passive"))
    )
    (net (code "158") (name "Net-(U8-RST_{slash}_PB5{slash}ADC0{slash}PINT5)") (class "Default")
      (node (ref "R42") (pin "2") (pinfunction "2_2") (pintype "passive"))
      (node (ref "U8") (pin "1") (pinfunction "RST_/_PB5/ADC0/PINT5_1") (pintype "input"))
    )
    (net (code "159") (name "Net-(U9-CBUS1)") (class "Default")
      (node (ref "R82") (pin "2") (pinfunction "2_2") (pintype "passive"))
      (node (ref "U9") (pin "14") (pinfunction "CBUS1_14") (pintype "passive"))
    )
    (net (code "160") (name "Net-(U9-CBUS2)") (class "Default")
      (node (ref "R79") (pin "1") (pinfunction "1_1") (pintype "passive"))
      (node (ref "U9") (pin "7") (pinfunction "CBUS2_7") (pintype "passive"))
    )
    (net (code "161") (name "Net-(U9-CBUS3)") (class "Default")
      (node (ref "R88") (pin "1") (pinfunction "1_1") (pintype "passive"))
      (node (ref "R90") (pin "2") (pinfunction "2_2") (pintype "passive"))
      (node (ref "U9") (pin "16") (pinfunction "CBUS3_16") (pintype "passive"))
    )
    (net (code "162") (name "Net-(U9-RXD)") (class "Default")
      (node (ref "R81") (pin "2") (pinfunction "2_2") (pintype "passive"))
      (node (ref "U9") (pin "4") (pinfunction "RXD_4") (pintype "input"))
    )
    (net (code "163") (name "Net-(U9-TXD)") (class "Default")
      (node (ref "R80") (pin "2") (pinfunction "2_2") (pintype "passive"))
      (node (ref "U9") (pin "1") (pinfunction "TXD_1") (pintype "output"))
    )
    (net (code "164") (name "Net-(Z3-RED)") (class "Default")
      (node (ref "C52") (pin "1") (pintype "passive"))
      (node (ref "C53") (pin "1") (pintype "passive"))
      (node (ref "L9") (pin "2") (pintype "passive"))
      (node (ref "Z3") (pin "1") (pinfunction "RED_1") (pintype "passive"))
    )
    (net (code "165") (name "SW5") (class "Default")
      (node (ref "J10") (pin "2") (pinfunction "2_2") (pintype "passive"))
      (node (ref "Q1") (pin "D") (pintype "passive"))
      (node (ref "R19") (pin "1") (pinfunction "1_1") (pintype "passive"))
    )
    (net (code "166") (name "unconnected-(FID1-Pad0)") (class "Default")
      (node (ref "FID1") (pin "0") (pinfunction "0_0") (pintype "passive+no_connect"))
    )
    (net (code "167") (name "unconnected-(FID1-Pad1)") (class "Default")
      (node (ref "FID1") (pin "1") (pinfunction "1_1") (pintype "passive+no_connect"))
    )
    (net (code "168") (name "unconnected-(FID2-Pad0)") (class "Default")
      (node (ref "FID2") (pin "0") (pinfunction "0_0") (pintype "passive+no_connect"))
    )
    (net (code "169") (name "unconnected-(FID2-Pad1)") (class "Default")
      (node (ref "FID2") (pin "1") (pinfunction "1_1") (pintype "passive+no_connect"))
    )
    (net (code "170") (name "unconnected-(FID3-Pad0)") (class "Default")
      (node (ref "FID3") (pin "0") (pinfunction "0_0") (pintype "passive+no_connect"))
    )
    (net (code "171") (name "unconnected-(FID3-Pad1)") (class "Default")
      (node (ref "FID3") (pin "1") (pinfunction "1_1") (pintype "passive+no_connect"))
    )
    (net (code "172") (name "unconnected-(FID4-Pad0)") (class "Default")
      (node (ref "FID4") (pin "0") (pinfunction "0_0") (pintype "passive+no_connect"))
    )
    (net (code "173") (name "unconnected-(FID4-Pad1)") (class "Default")
      (node (ref "FID4") (pin "1") (pinfunction "1_1") (pintype "passive+no_connect"))
    )
    (net (code "174") (name "unconnected-(J13-Pad1)") (class "Default")
      (node (ref "J13") (pin "1") (pinfunction "1_1") (pintype "passive+no_connect"))
    )
    (net (code "175") (name "unconnected-(PFID1-Pad0)") (class "Default")
      (node (ref "PFID1") (pin "0") (pinfunction "0_0") (pintype "passive+no_connect"))
    )
    (net (code "176") (name "unconnected-(PFID1-Pad1)") (class "Default")
      (node (ref "PFID1") (pin "1") (pinfunction "1_1") (pintype "passive+no_connect"))
    )
    (net (code "177") (name "unconnected-(PFID2-Pad0)") (class "Default")
      (node (ref "PFID2") (pin "0") (pinfunction "0_0") (pintype "passive+no_connect"))
    )
    (net (code "178") (name "unconnected-(PFID2-Pad1)") (class "Default")
      (node (ref "PFID2") (pin "1") (pinfunction "1_1") (pintype "passive+no_connect"))
    )
    (net (code "179") (name "unconnected-(U7-GPIO0-Pad48)") (class "Default")
      (node (ref "U7") (pin "48") (pinfunction "GPIO0_48") (pintype "passive+no_connect"))
    )
    (net (code "180") (name "unconnected-(U7-GPIO1-Pad45)") (class "Default")
      (node (ref "U7") (pin "45") (pinfunction "GPIO1_45") (pintype "passive+no_connect"))
    )
    (net (code "181") (name "unconnected-(U7-GPIO2-Pad44)") (class "Default")
      (node (ref "U7") (pin "44") (pinfunction "GPIO2_44") (pintype "passive+no_connect"))
    )
    (net (code "182") (name "unconnected-(U7-GPIO3-Pad43)") (class "Default")
      (node (ref "U7") (pin "43") (pinfunction "GPIO3_43") (pintype "passive+no_connect"))
    )
    (net (code "183") (name "unconnected-(U7-GPIO4-Pad42)") (class "Default")
      (node (ref "U7") (pin "42") (pinfunction "GPIO4_42") (pintype "passive+no_connect"))
    )
    (net (code "184") (name "unconnected-(U7-GPIO5-Pad41)") (class "Default")
      (node (ref "U7") (pin "41") (pinfunction "GPIO5_41") (pintype "passive+no_connect"))
    )
    (net (code "185") (name "unconnected-(U7-GPIO6-Pad38)") (class "Default")
      (node (ref "U7") (pin "38") (pinfunction "GPIO6_38") (pintype "passive+no_connect"))
    )
    (net (code "186") (name "unconnected-(U7-GPIO7-Pad37)") (class "Default")
      (node (ref "U7") (pin "37") (pinfunction "GPIO7_37") (pintype "passive+no_connect"))
    )
    (net (code "187") (name "unconnected-(U7-GPIO8-Pad36)") (class "Default")
      (node (ref "U7") (pin "36") (pinfunction "GPIO8_36") (pintype "passive+no_connect"))
    )
    (net (code "188") (name "unconnected-(U7-GPIO10-Pad34)") (class "Default")
      (node (ref "U7") (pin "34") (pinfunction "GPIO10_34") (pintype "passive+no_connect"))
    )
    (net (code "189") (name "unconnected-(U7-GPIO11-Pad33)") (class "Default")
      (node (ref "U7") (pin "33") (pinfunction "GPIO11_33") (pintype "passive+no_connect"))
    )
    (net (code "190") (name "unconnected-(U7-GPIO16-Pad3)") (class "Default")
      (node (ref "U7") (pin "3") (pinfunction "GPIO16_3") (pintype "passive+no_connect"))
    )
    (net (code "191") (name "unconnected-(U7-GPIO17-Pad2)") (class "Default")
      (node (ref "U7") (pin "2") (pinfunction "GPIO17_2") (pintype "passive+no_connect"))
    )
    (net (code "192") (name "unconnected-(U7-SPDIF_O-Pad1)") (class "Default")
      (node (ref "U7") (pin "1") (pinfunction "SPDIF_O_1") (pintype "passive+no_connect"))
    )
    (net (code "193") (name "unconnected-(U7-TEST-Pad5)") (class "Default")
      (node (ref "U7") (pin "5") (pinfunction "TEST_5") (pintype "passive+no_connect"))
    )
    (net (code "194") (name "unconnected-(Z1-Pad1)") (class "Default")
      (node (ref "Z1") (pin "1") (pinfunction "1_1") (pintype "passive+no_connect"))
    )
    (net (code "195") (name "unconnected-(Z1-Pad2)") (class "Default")
      (node (ref "Z1") (pin "2") (pinfunction "2_2") (pintype "passive+no_connect"))
    )
    (net (code "196") (name "unconnected-(Z1-Pad3)") (class "Default")
      (node (ref "Z1") (pin "3") (pinfunction "3_3") (pintype "passive+no_connect"))
    )
    (net (code "197") (name "unconnected-(Z1-Pad4)") (class "Default")
      (node (ref "Z1") (pin "4") (pinfunction "4_4") (pintype "passive+no_connect"))
    )
    (net (code "198") (name "unconnected-(Z1-Pad5)") (class "Default")
      (node (ref "Z1") (pin "5") (pinfunction "5_5") (pintype "passive+no_connect"))
    )
    (net (code "199") (name "unconnected-(Z1-Pad6)") (class "Default")
      (node (ref "Z1") (pin "6") (pinfunction "6_6") (pintype "passive+no_connect"))
    )
    (net (code "200") (name "unconnected-(Z1-Pad7)") (class "Default")
      (node (ref "Z1") (pin "7") (pinfunction "7_7") (pintype "passive+no_connect"))
    )
    (net (code "201") (name "unconnected-(Z1-Pad8)") (class "Default")
      (node (ref "Z1") (pin "8") (pinfunction "8_8") (pintype "passive+no_connect"))
    )
    (net (code "202") (name "unconnected-(Z1-Pad9)") (class "Default")
      (node (ref "Z1") (pin "9") (pinfunction "9_9") (pintype "passive+no_connect"))
    )
    (net (code "203") (name "unconnected-(Z1-Pad10)") (class "Default")
      (node (ref "Z1") (pin "10") (pinfunction "10_10") (pintype "passive+no_connect"))
    )
    (net (code "204") (name "unconnected-(Z1-Pad11)") (class "Default")
      (node (ref "Z1") (pin "11") (pinfunction "11_11") (pintype "passive+no_connect"))
    )
    (net (code "205") (name "unconnected-(Z1-Pad12)") (class "Default")
      (node (ref "Z1") (pin "12") (pinfunction "12_12") (pintype "passive+no_connect"))
    )
    (net (code "206") (name "unconnected-(Z1-Pad13)") (class "Default")
      (node (ref "Z1") (pin "13") (pinfunction "13_13") (pintype "passive+no_connect"))
    )
    (net (code "207") (name "unconnected-(Z1-Pad14)") (class "Default")
      (node (ref "Z1") (pin "14") (pinfunction "14_14") (pintype "passive+no_connect"))
    )
    (net (code "208") (name "unconnected-(Z1-Pad15)") (class "Default")
      (node (ref "Z1") (pin "15") (pinfunction "15_15") (pintype "passive+no_connect"))
    )
    (net (code "209") (name "unconnected-(Z1-Pad16)") (class "Default")
      (node (ref "Z1") (pin "16") (pinfunction "16_16") (pintype "passive+no_connect"))
    )
    (net (code "210") (name "unconnected-(Z1-Pad17)") (class "Default")
      (node (ref "Z1") (pin "17") (pinfunction "17_17") (pintype "passive+no_connect"))
    )
    (net (code "211") (name "unconnected-(Z1-Pad18)") (class "Default")
      (node (ref "Z1") (pin "18") (pinfunction "18_18") (pintype "passive+no_connect"))
    )
    (net (code "212") (name "unconnected-(Z1-Pad19)") (class "Default")
      (node (ref "Z1") (pin "19") (pinfunction "19_19") (pintype "passive+no_connect"))
    )
    (net (code "213") (name "unconnected-(Z1-Pad20)") (class "Default")
      (node (ref "Z1") (pin "20") (pinfunction "20_20") (pintype "passive+no_connect"))
    )
    (net (code "214") (name "unconnected-(Z1-Pad21)") (class "Default")
      (node (ref "Z1") (pin "21") (pinfunction "21_21") (pintype "passive+no_connect"))
    )
    (net (code "215") (name "unconnected-(Z1-Pad22)") (class "Default")
      (node (ref "Z1") (pin "22") (pinfunction "22_22") (pintype "passive+no_connect"))
    )
    (net (code "216") (name "unconnected-(Z1-Pad23)") (class "Default")
      (node (ref "Z1") (pin "23") (pinfunction "23_23") (pintype "passive+no_connect"))
    )
    (net (code "217") (name "unconnected-(Z1-Pad24)") (class "Default")
      (node (ref "Z1") (pin "24") (pinfunction "24_24") (pintype "passive+no_connect"))
    )
    (net (code "218") (name "unconnected-(Z1-Pad25)") (class "Default")
      (node (ref "Z1") (pin "25") (pinfunction "25_25") (pintype "passive+no_connect"))
    )
    (net (code "219") (name "unconnected-(Z1-Pad26)") (class "Default")
      (node (ref "Z1") (pin "26") (pinfunction "26_26") (pintype "passive+no_connect"))
    )
    (net (code "220") (name "unconnected-(Z1-Pad27)") (class "Default")
      (node (ref "Z1") (pin "27") (pinfunction "27_27") (pintype "passive+no_connect"))
    )
    (net (code "221") (name "unconnected-(Z1-Pad28)") (class "Default")
      (node (ref "Z1") (pin "28") (pinfunction "28_28") (pintype "passive+no_connect"))
    )
    (net (code "222") (name "unconnected-(Z1-Pad29)") (class "Default")
      (node (ref "Z1") (pin "29") (pinfunction "29_29") (pintype "passive+no_connect"))
    )
    (net (code "223") (name "unconnected-(Z1-Pad30)") (class "Default")
      (node (ref "Z1") (pin "30") (pinfunction "30_30") (pintype "passive+no_connect"))
    )
    (net (code "224") (name "unconnected-(Z1-Pad31)") (class "Default")
      (node (ref "Z1") (pin "31") (pinfunction "31_31") (pintype "passive+no_connect"))
    )
    (net (code "225") (name "unconnected-(Z1-Pad32)") (class "Default")
      (node (ref "Z1") (pin "32") (pinfunction "32_32") (pintype "passive+no_connect"))
    )
    (net (code "226") (name "unconnected-(Z1-Pad33)") (class "Default")
      (node (ref "Z1") (pin "33") (pinfunction "33_33") (pintype "passive+no_connect"))
    )
    (net (code "227") (name "unconnected-(Z1-Pad34)") (class "Default")
      (node (ref "Z1") (pin "34") (pinfunction "34_34") (pintype "passive+no_connect"))
    )
    (net (code "228") (name "unconnected-(Z1-Pad35)") (class "Default")
      (node (ref "Z1") (pin "35") (pinfunction "35_35") (pintype "passive+no_connect"))
    )
    (net (code "229") (name "unconnected-(Z1-Pad36)") (class "Default")
      (node (ref "Z1") (pin "36") (pinfunction "36_36") (pintype "passive+no_connect"))
    )
    (net (code "230") (name "unconnected-(Z1-Pad37)") (class "Default")
      (node (ref "Z1") (pin "37") (pinfunction "37_37") (pintype "passive+no_connect"))
    )
    (net (code "231") (name "unconnected-(Z1-Pad38)") (class "Default")
      (node (ref "Z1") (pin "38") (pinfunction "38_38") (pintype "passive+no_connect"))
    )
    (net (code "232") (name "unconnected-(Z1-Pad39)") (class "Default")
      (node (ref "Z1") (pin "39") (pinfunction "39_39") (pintype "passive+no_connect"))
    )
    (net (code "233") (name "unconnected-(Z1-Pad40)") (class "Default")
      (node (ref "Z1") (pin "40") (pinfunction "40_40") (pintype "passive+no_connect"))
    )
    (net (code "234") (name "unconnected-(Z2-Pad1)") (class "Default")
      (node (ref "Z2") (pin "1") (pinfunction "1_1") (pintype "passive+no_connect"))
    )
    (net (code "235") (name "unconnected-(Z2-Pad2)") (class "Default")
      (node (ref "Z2") (pin "2") (pinfunction "2_2") (pintype "passive+no_connect"))
    )
    (net (code "236") (name "unconnected-(Z2-Pad4)") (class "Default")
      (node (ref "Z2") (pin "4") (pinfunction "4_4") (pintype "passive+no_connect"))
    )
    (net (code "237") (name "unconnected-(Z2-Pad8)") (class "Default")
      (node (ref "Z2") (pin "8") (pinfunction "8_8") (pintype "passive+no_connect"))
    )
    (net (code "238") (name "unconnected-(Z2-Pad10)") (class "Default")
      (node (ref "Z2") (pin "10") (pinfunction "10_10") (pintype "passive+no_connect"))
    )
    (net (code "239") (name "unconnected-(Z2-Pad11)") (class "Default")
      (node (ref "Z2") (pin "11") (pinfunction "11_11") (pintype "passive+no_connect"))
    )
    (net (code "240") (name "unconnected-(Z2-Pad14)") (class "Default")
      (node (ref "Z2") (pin "14") (pinfunction "14_14") (pintype "passive+no_connect"))
    )
    (net (code "241") (name "unconnected-(Z2-Pad16)") (class "Default")
      (node (ref "Z2") (pin "16") (pinfunction "16_16") (pintype "passive+no_connect"))
    )
    (net (code "242") (name "unconnected-(Z2-Pad17)") (class "Default")
      (node (ref "Z2") (pin "17") (pinfunction "17_17") (pintype "passive+no_connect"))
    )
    (net (code "243") (name "unconnected-(Z2-Pad20)") (class "Default")
      (node (ref "Z2") (pin "20") (pinfunction "20_20") (pintype "passive+no_connect"))
    )
    (net (code "244") (name "unconnected-(Z2-Pad22)") (class "Default")
      (node (ref "Z2") (pin "22") (pinfunction "22_22") (pintype "passive+no_connect"))
    )
    (net (code "245") (name "unconnected-(Z2-Pad24)") (class "Default")
      (node (ref "Z2") (pin "24") (pinfunction "24_24") (pintype "passive+no_connect"))
    )
    (net (code "246") (name "unconnected-(Z2-Pad25)") (class "Default")
      (node (ref "Z2") (pin "25") (pinfunction "25_25") (pintype "passive+no_connect"))
    )
    (net (code "247") (name "unconnected-(Z2-Pad26)") (class "Default")
      (node (ref "Z2") (pin "26") (pinfunction "26_26") (pintype "passive+no_connect"))
    )
    (net (code "248") (name "unconnected-(Z2-Pad27)") (class "Default")
      (node (ref "Z2") (pin "27") (pinfunction "27_27") (pintype "passive+no_connect"))
    )
    (net (code "249") (name "unconnected-(Z2-Pad28)") (class "Default")
      (node (ref "Z2") (pin "28") (pinfunction "28_28") (pintype "passive+no_connect"))
    )
    (net (code "250") (name "unconnected-(Z2-Pad30)") (class "Default")
      (node (ref "Z2") (pin "30") (pinfunction "30_30") (pintype "passive+no_connect"))
    )
    (net (code "251") (name "unconnected-(Z2-Pad38)") (class "Default")
      (node (ref "Z2") (pin "38") (pinfunction "38_38") (pintype "passive+no_connect"))
    )
    (net (code "252") (name "unconnected-(Z3-YELLOW-Pad2)") (class "Default")
      (node (ref "Z3") (pin "2") (pinfunction "YELLOW_2") (pintype "passive+no_connect"))
    )
  )
)
